# ECG_NEMO_final.net
KiCad netlist of a schematic drawn in Altium Designer
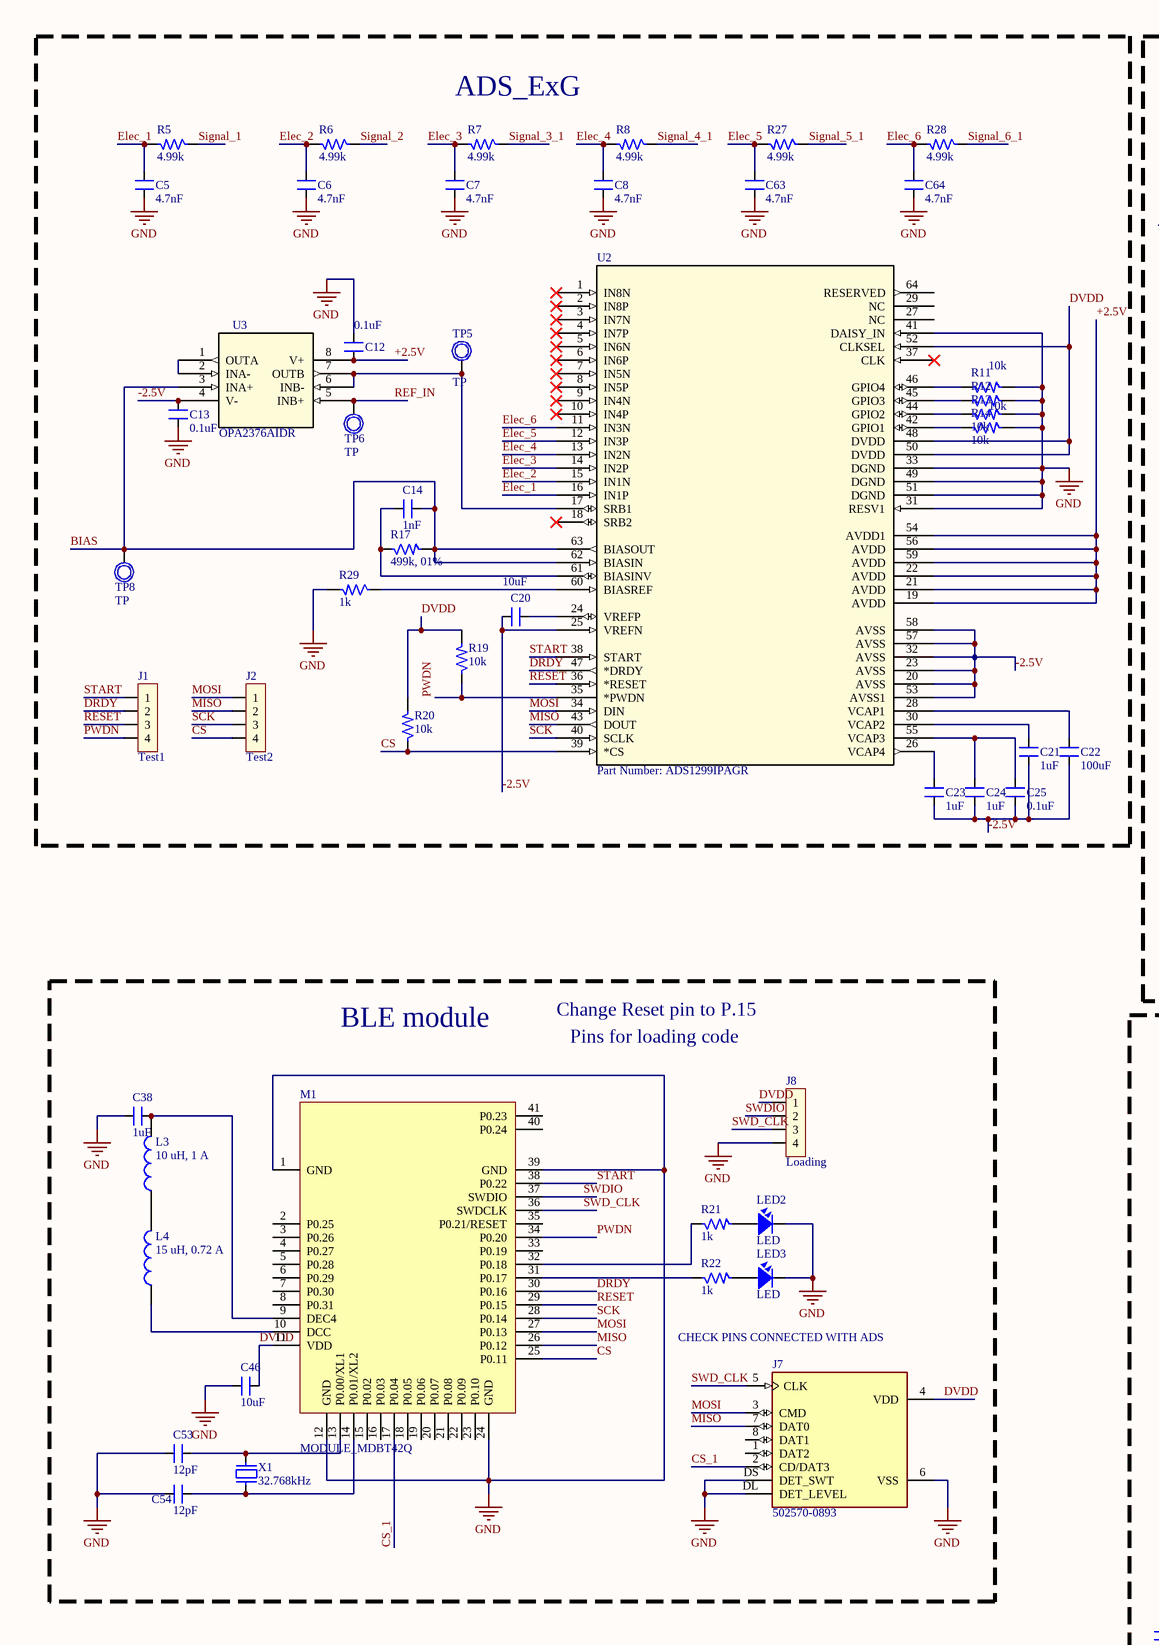
[diagram p0: ECG_NEMO_final.schdoc, left]
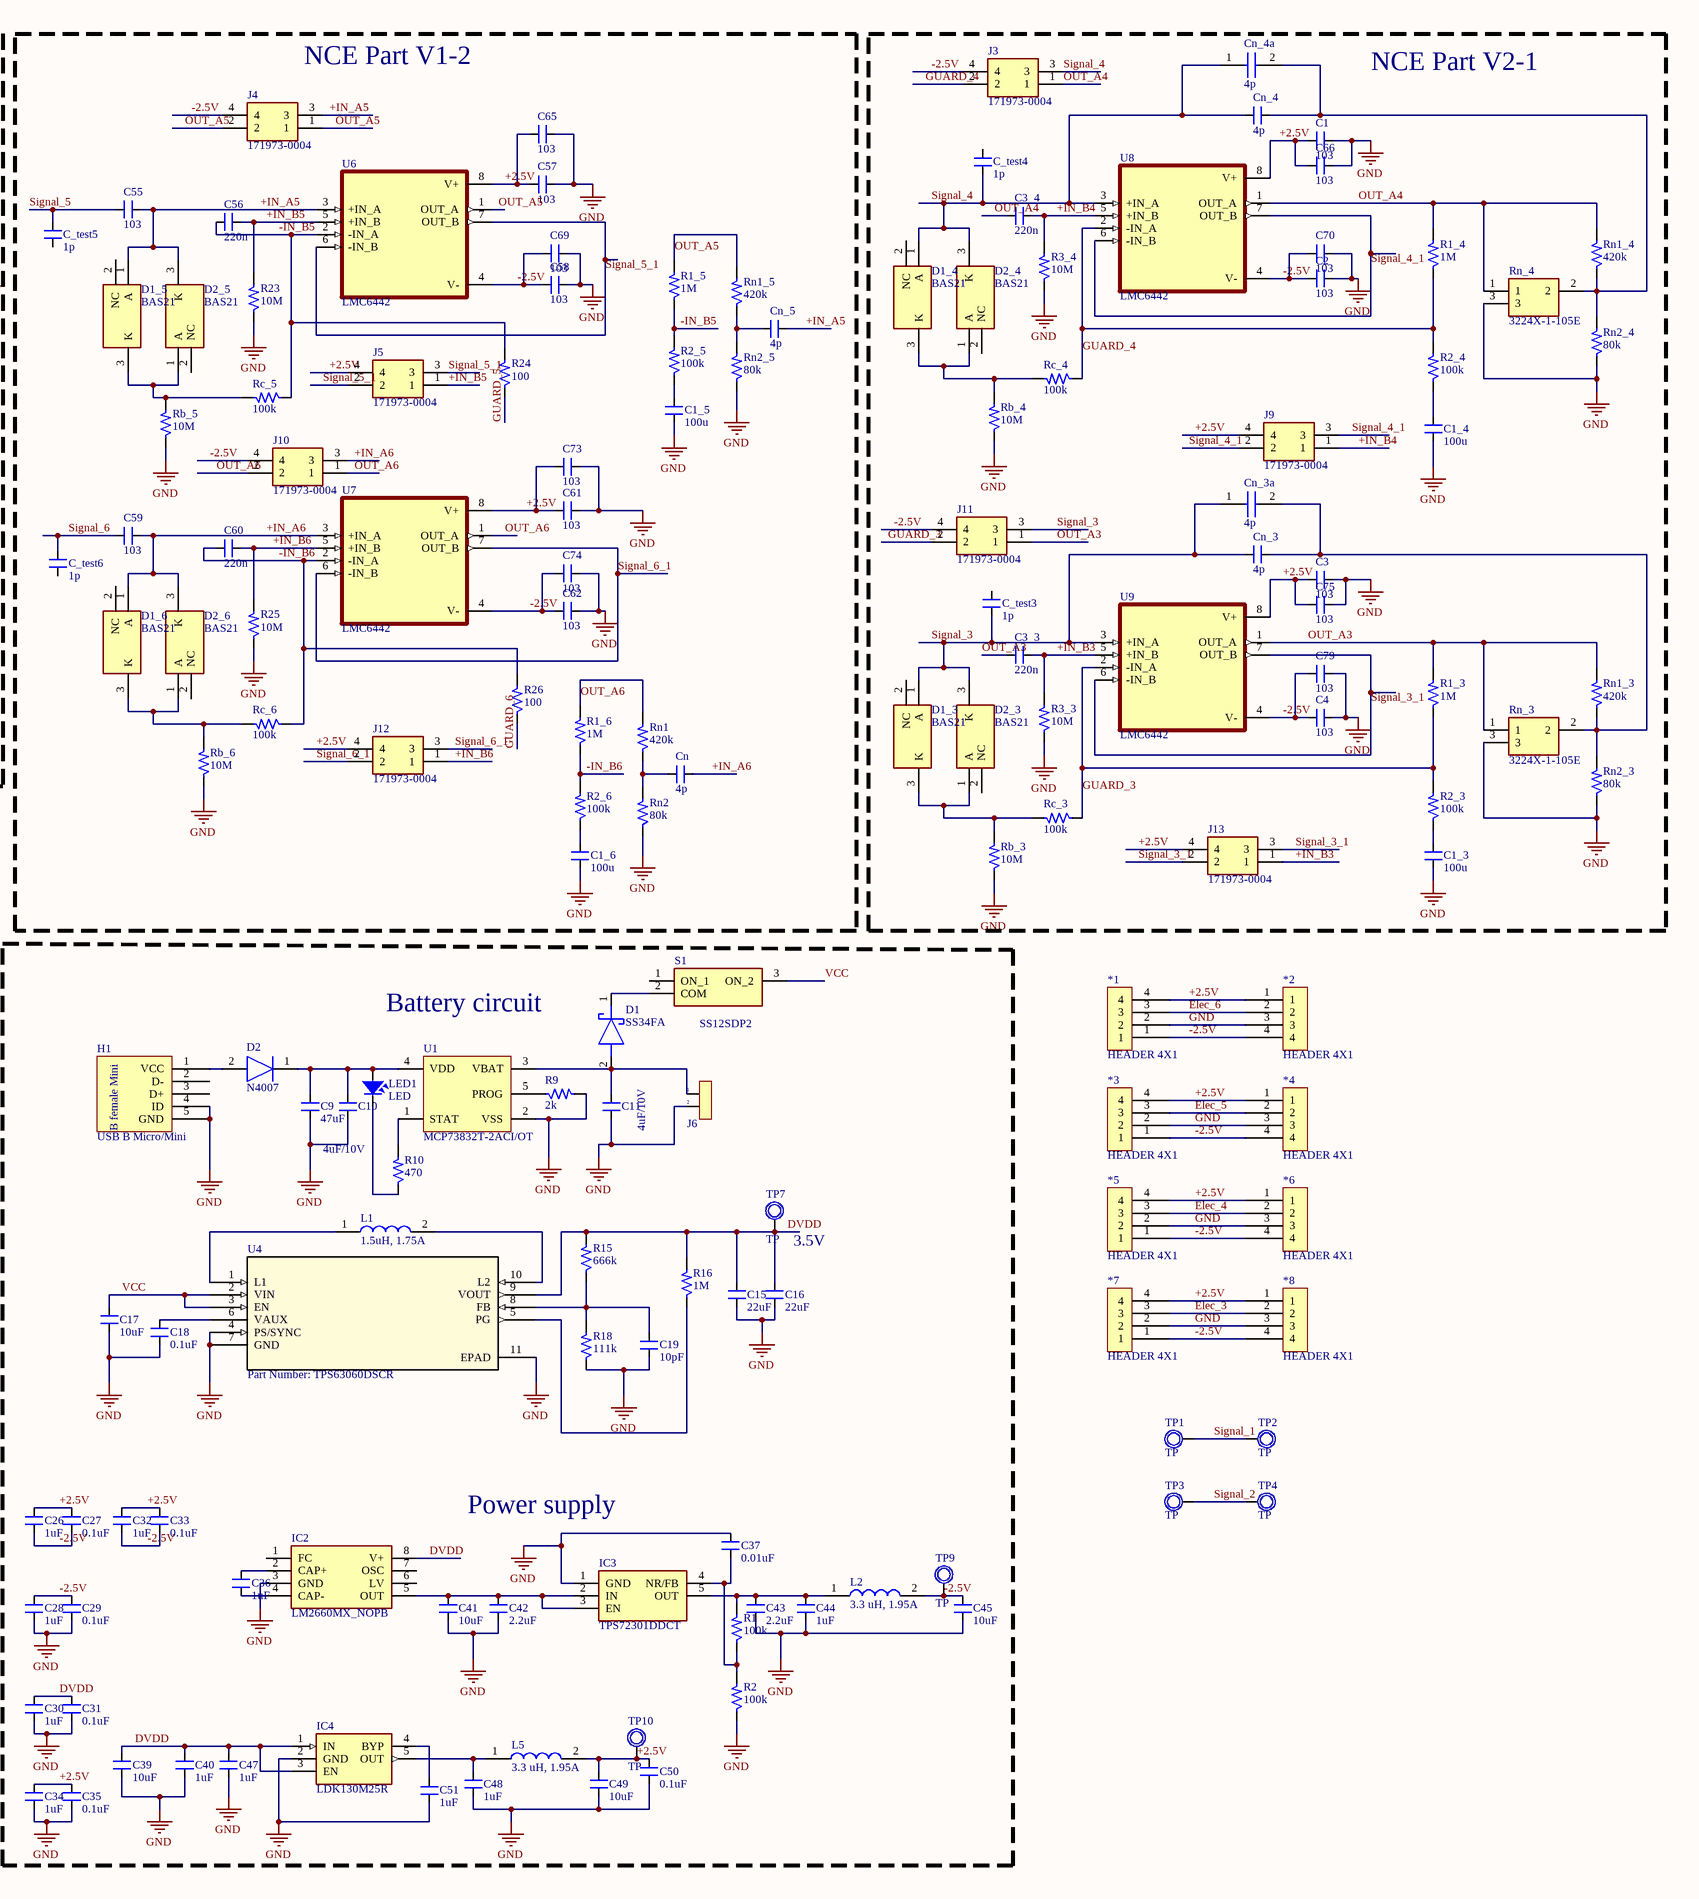
[diagram p1: ECG_NEMO_final.schdoc, right]

(export (version "E")
  (design (tool "Eeschema 10.0.6"))
  (components
    (comp (ref "*1") (value "HEADER 4X1") (footprint "HEADER4X1") (libsource (lib "") (part "HEADER 4X1_1")))
    (comp (ref "*2")
      (value "HEADER 4X1")
      (footprint "HEADER4X1")
      (libsource (lib "TechMT.VN_Lib_Project v1.0") (part "HEADER 4X1"))
    )
    (comp (ref "*3") (value "HEADER 4X1") (footprint "HEADER4X1") (libsource (lib "") (part "HEADER 4X1_1")))
    (comp (ref "*4")
      (value "HEADER 4X1")
      (footprint "HEADER4X1")
      (libsource (lib "TechMT.VN_Lib_Project v1.0") (part "HEADER 4X1"))
    )
    (comp (ref "*5") (value "HEADER 4X1") (footprint "HEADER4X1") (libsource (lib "") (part "HEADER 4X1_1")))
    (comp (ref "*6")
      (value "HEADER 4X1")
      (footprint "HEADER4X1")
      (libsource (lib "TechMT.VN_Lib_Project v1.0") (part "HEADER 4X1"))
    )
    (comp (ref "*7") (value "HEADER 4X1") (footprint "HEADER4X1") (libsource (lib "") (part "HEADER 4X1_1")))
    (comp (ref "*8")
      (value "HEADER 4X1")
      (footprint "HEADER4X1")
      (libsource (lib "TechMT.VN_Lib_Project v1.0") (part "HEADER 4X1"))
    )
    (comp (ref "C1")
      (value "103")
      (footprint "SM-0805")
      (description "Cap SMD")
      (libsource (lib "VioletofSun") (part "CM"))
    )
    (comp (ref "C1_3")
      (value "100u")
      (footprint "SM-0805")
      (description "Cap SMD")
      (libsource (lib "VioletofSun") (part "CM"))
    )
    (comp (ref "C1_4")
      (value "100u")
      (footprint "SM-0805")
      (description "Cap SMD")
      (libsource (lib "VioletofSun") (part "CM"))
    )
    (comp (ref "C1_5")
      (value "100u")
      (footprint "SM-0805")
      (description "Cap SMD")
      (libsource (lib "VioletofSun") (part "CM"))
    )
    (comp (ref "C1_6")
      (value "100u")
      (footprint "SM-0805")
      (description "Cap SMD")
      (libsource (lib "VioletofSun") (part "CM"))
    )
    (comp (ref "C2")
      (value "103")
      (footprint "SM-0805")
      (description "Cap SMD")
      (libsource (lib "VioletofSun") (part "CM"))
    )
    (comp (ref "C3")
      (value "103")
      (footprint "SM-0805")
      (description "Cap SMD")
      (libsource (lib "VioletofSun") (part "CM"))
    )
    (comp (ref "C3_3")
      (value "220n")
      (footprint "SM-0805")
      (description "Cap SMD")
      (libsource (lib "VioletofSun") (part "CM"))
    )
    (comp (ref "C3_4")
      (value "220n")
      (footprint "SM-0805")
      (description "Cap SMD")
      (libsource (lib "VioletofSun") (part "CM"))
    )
    (comp (ref "C4")
      (value "103")
      (footprint "SM-0805")
      (description "Cap SMD")
      (libsource (lib "VioletofSun") (part "CM"))
    )
    (comp (ref "C5")
      (value "4.7nF")
      (footprint "SM-0805")
      (description "Cap SMD")
      (libsource (lib "VioletofSun") (part "CM"))
    )
    (comp (ref "C6")
      (value "4.7nF")
      (footprint "SM-0805")
      (description "Cap SMD")
      (libsource (lib "VioletofSun") (part "CM"))
    )
    (comp (ref "C7")
      (value "4.7nF")
      (footprint "SM-0805")
      (description "Cap SMD")
      (libsource (lib "VioletofSun") (part "CM"))
    )
    (comp (ref "C8")
      (value "4.7nF")
      (footprint "SM-0805")
      (description "Cap SMD")
      (libsource (lib "VioletofSun") (part "CM"))
    )
    (comp (ref "C9")
      (value "47uF")
      (footprint "SM-0805")
      (description "Cap SMD")
      (libsource (lib "VioletofSun") (part "CM"))
    )
    (comp (ref "C10")
      (value "4uF/10V")
      (footprint "SM-0805")
      (description "Cap SMD")
      (libsource (lib "VioletofSun") (part "CM"))
    )
    (comp (ref "C11")
      (value "4uF/10V")
      (footprint "SM-0805")
      (description "Cap SMD")
      (libsource (lib "VioletofSun") (part "CM"))
    )
    (comp (ref "C12")
      (value "0.1uF")
      (footprint "SM-0805")
      (description "Cap SMD")
      (libsource (lib "VioletofSun") (part "CM"))
    )
    (comp (ref "C13")
      (value "0.1uF")
      (footprint "SM-0805")
      (description "Cap SMD")
      (libsource (lib "VioletofSun") (part "CM"))
    )
    (comp (ref "C14")
      (value "1nF")
      (footprint "SM-0805")
      (description "Cap SMD")
      (libsource (lib "VioletofSun") (part "CM"))
    )
    (comp (ref "C15")
      (value "22uF")
      (footprint "SM-0805")
      (description "Cap SMD")
      (libsource (lib "VioletofSun") (part "CM"))
    )
    (comp (ref "C16")
      (value "22uF")
      (footprint "SM-0805")
      (description "Cap SMD")
      (libsource (lib "VioletofSun") (part "CM"))
    )
    (comp (ref "C17")
      (value "10uF")
      (footprint "SM-0805")
      (description "Cap SMD")
      (libsource (lib "VioletofSun") (part "CM"))
    )
    (comp (ref "C18")
      (value "0.1uF")
      (footprint "SM-0805")
      (description "Cap SMD")
      (libsource (lib "VioletofSun") (part "CM"))
    )
    (comp (ref "C19")
      (value "10pF")
      (footprint "SM-0805")
      (description "Cap SMD")
      (libsource (lib "VioletofSun") (part "CM"))
    )
    (comp (ref "C20")
      (value "10uF")
      (footprint "SM-0805")
      (description "Cap SMD")
      (libsource (lib "VioletofSun") (part "CM"))
    )
    (comp (ref "C21")
      (value "1uF")
      (footprint "SM-0805")
      (description "Cap SMD")
      (libsource (lib "VioletofSun") (part "CM"))
    )
    (comp (ref "C22")
      (value "100uF")
      (footprint "SM-0805")
      (description "Cap SMD")
      (libsource (lib "VioletofSun") (part "CM"))
    )
    (comp (ref "C23")
      (value "1uF")
      (footprint "SM-0805")
      (description "Cap SMD")
      (libsource (lib "VioletofSun") (part "CM"))
    )
    (comp (ref "C24")
      (value "1uF")
      (footprint "SM-0805")
      (description "Cap SMD")
      (libsource (lib "VioletofSun") (part "CM"))
    )
    (comp (ref "C25")
      (value "0.1uF")
      (footprint "SM-0805")
      (description "Cap SMD")
      (libsource (lib "VioletofSun") (part "CM"))
    )
    (comp (ref "C26")
      (value "1uF")
      (footprint "SM-0805")
      (description "Cap SMD")
      (libsource (lib "VioletofSun") (part "CM"))
    )
    (comp (ref "C27")
      (value "0.1uF")
      (footprint "SM-0805")
      (description "Cap SMD")
      (libsource (lib "VioletofSun") (part "CM"))
    )
    (comp (ref "C28")
      (value "1uF")
      (footprint "SM-0805")
      (description "Cap SMD")
      (libsource (lib "VioletofSun") (part "CM"))
    )
    (comp (ref "C29")
      (value "0.1uF")
      (footprint "SM-0805")
      (description "Cap SMD")
      (libsource (lib "VioletofSun") (part "CM"))
    )
    (comp (ref "C30")
      (value "1uF")
      (footprint "SM-0805")
      (description "Cap SMD")
      (libsource (lib "VioletofSun") (part "CM"))
    )
    (comp (ref "C31")
      (value "0.1uF")
      (footprint "SM-0805")
      (description "Cap SMD")
      (libsource (lib "VioletofSun") (part "CM"))
    )
    (comp (ref "C32")
      (value "1uF")
      (footprint "SM-0805")
      (description "Cap SMD")
      (libsource (lib "VioletofSun") (part "CM"))
    )
    (comp (ref "C33")
      (value "0.1uF")
      (footprint "SM-0805")
      (description "Cap SMD")
      (libsource (lib "VioletofSun") (part "CM"))
    )
    (comp (ref "C34")
      (value "1uF")
      (footprint "SM-0805")
      (description "Cap SMD")
      (libsource (lib "VioletofSun") (part "CM"))
    )
    (comp (ref "C35")
      (value "0.1uF")
      (footprint "SM-0805")
      (description "Cap SMD")
      (libsource (lib "VioletofSun") (part "CM"))
    )
    (comp (ref "C36")
      (value "1uF")
      (footprint "SM-0805")
      (description "Cap SMD")
      (libsource (lib "VioletofSun") (part "CM"))
    )
    (comp (ref "C37")
      (value "0.01uF")
      (footprint "SM-0805")
      (description "Cap SMD")
      (libsource (lib "VioletofSun") (part "CM"))
    )
    (comp (ref "C38")
      (value "1uF")
      (footprint "SM-0805")
      (description "Cap SMD")
      (libsource (lib "VioletofSun") (part "CM"))
    )
    (comp (ref "C39")
      (value "10uF")
      (footprint "SM-0805")
      (description "Cap SMD")
      (libsource (lib "VioletofSun") (part "CM"))
    )
    (comp (ref "C40")
      (value "1uF")
      (footprint "SM-0805")
      (description "Cap SMD")
      (libsource (lib "VioletofSun") (part "CM"))
    )
    (comp (ref "C41")
      (value "10uF")
      (footprint "SM-0805")
      (description "Cap SMD")
      (libsource (lib "VioletofSun") (part "CM"))
    )
    (comp (ref "C42")
      (value "2.2uF")
      (footprint "SM-0805")
      (description "Cap SMD")
      (libsource (lib "VioletofSun") (part "CM"))
    )
    (comp (ref "C43")
      (value "2.2uF")
      (footprint "SM-0805")
      (description "Cap SMD")
      (libsource (lib "VioletofSun") (part "CM"))
    )
    (comp (ref "C44")
      (value "1uF")
      (footprint "SM-0805")
      (description "Cap SMD")
      (libsource (lib "VioletofSun") (part "CM"))
    )
    (comp (ref "C45")
      (value "10uF")
      (footprint "SM-0805")
      (description "Cap SMD")
      (libsource (lib "VioletofSun") (part "CM"))
    )
    (comp (ref "C46")
      (value "10uF")
      (footprint "SM-0805")
      (description "Cap SMD")
      (libsource (lib "VioletofSun") (part "CM"))
    )
    (comp (ref "C47")
      (value "1uF")
      (footprint "SM-0805")
      (description "Cap SMD")
      (libsource (lib "VioletofSun") (part "CM"))
    )
    (comp (ref "C48")
      (value "1uF")
      (footprint "SM-0805")
      (description "Cap SMD")
      (libsource (lib "VioletofSun") (part "CM"))
    )
    (comp (ref "C49")
      (value "10uF")
      (footprint "SM-0805")
      (description "Cap SMD")
      (libsource (lib "VioletofSun") (part "CM"))
    )
    (comp (ref "C50")
      (value "0.1uF")
      (footprint "SM-0805")
      (description "Cap SMD")
      (libsource (lib "VioletofSun") (part "CM"))
    )
    (comp (ref "C51")
      (value "1uF")
      (footprint "SM-0805")
      (description "Cap SMD")
      (libsource (lib "VioletofSun") (part "CM"))
    )
    (comp (ref "C53")
      (value "12pF")
      (footprint "SM-0805")
      (description "Cap SMD")
      (libsource (lib "VioletofSun") (part "CM"))
    )
    (comp (ref "C54")
      (value "12pF")
      (footprint "SM-0805")
      (description "Cap SMD")
      (libsource (lib "VioletofSun") (part "CM"))
    )
    (comp (ref "C55")
      (value "103")
      (footprint "SM-0805")
      (description "Cap SMD")
      (libsource (lib "Free Documents") (part "CM_5"))
    )
    (comp (ref "C56")
      (value "220n")
      (footprint "SM-0805")
      (description "Cap SMD")
      (libsource (lib "VioletofSun") (part "CM"))
    )
    (comp (ref "C57")
      (value "103")
      (footprint "SM-0805")
      (description "Cap SMD")
      (libsource (lib "VioletofSun") (part "CM"))
    )
    (comp (ref "C58")
      (value "103")
      (footprint "SM-0805")
      (description "Cap SMD")
      (libsource (lib "VioletofSun") (part "CM"))
    )
    (comp (ref "C59")
      (value "103")
      (footprint "SM-0805")
      (description "Cap SMD")
      (libsource (lib "VioletofSun") (part "CM"))
    )
    (comp (ref "C60")
      (value "220n")
      (footprint "SM-0805")
      (description "Cap SMD")
      (libsource (lib "VioletofSun") (part "CM"))
    )
    (comp (ref "C61")
      (value "103")
      (footprint "SM-0805")
      (description "Cap SMD")
      (libsource (lib "VioletofSun") (part "CM"))
    )
    (comp (ref "C62")
      (value "103")
      (footprint "SM-0805")
      (description "Cap SMD")
      (libsource (lib "VioletofSun") (part "CM"))
    )
    (comp (ref "C63")
      (value "4.7nF")
      (footprint "SM-0805")
      (description "Cap SMD")
      (libsource (lib "VioletofSun") (part "CM"))
    )
    (comp (ref "C64")
      (value "4.7nF")
      (footprint "SM-0805")
      (description "Cap SMD")
      (libsource (lib "VioletofSun") (part "CM"))
    )
    (comp (ref "C65")
      (value "103")
      (footprint "SM-0805")
      (description "Cap SMD")
      (libsource (lib "VioletofSun") (part "CM"))
    )
    (comp (ref "C66")
      (value "103")
      (footprint "SM-0805")
      (description "Cap SMD")
      (libsource (lib "VioletofSun") (part "CM"))
    )
    (comp (ref "C69")
      (value "103")
      (footprint "SM-0805")
      (description "Cap SMD")
      (libsource (lib "VioletofSun") (part "CM"))
    )
    (comp (ref "C70")
      (value "103")
      (footprint "SM-0805")
      (description "Cap SMD")
      (libsource (lib "VioletofSun") (part "CM"))
    )
    (comp (ref "C73")
      (value "103")
      (footprint "SM-0805")
      (description "Cap SMD")
      (libsource (lib "VioletofSun") (part "CM"))
    )
    (comp (ref "C74")
      (value "103")
      (footprint "SM-0805")
      (description "Cap SMD")
      (libsource (lib "VioletofSun") (part "CM"))
    )
    (comp (ref "C75")
      (value "103")
      (footprint "SM-0805")
      (description "Cap SMD")
      (libsource (lib "VioletofSun") (part "CM"))
    )
    (comp (ref "C79")
      (value "103")
      (footprint "SM-0805")
      (description "Cap SMD")
      (libsource (lib "VioletofSun") (part "CM"))
    )
    (comp (ref "Cn")
      (value "4p")
      (footprint "SM-0805")
      (description "Cap SMD")
      (libsource (lib "VioletofSun") (part "CM"))
    )
    (comp (ref "Cn_3")
      (value "4p")
      (footprint "SM-0805")
      (description "Cap SMD")
      (libsource (lib "VioletofSun") (part "CM"))
    )
    (comp (ref "Cn_3a")
      (value "4p")
      (footprint "Var_Cap-JZ100:JZ100")
      (description "Capacitor")
      (fields
        (field (name "MANUFACTURER_PART_NUMBER") "JZ100")
        (field (name "MOUSER PART NUMBER") "768-JZ100")
      )
      (libsource (lib "Var_Cap-JZ100") (part "JZ100"))
    )
    (comp (ref "Cn_4")
      (value "4p")
      (footprint "SM-0805")
      (description "Cap SMD")
      (libsource (lib "VioletofSun") (part "CM"))
    )
    (comp (ref "Cn_4a")
      (value "4p")
      (footprint "Var_Cap-JZ100:JZ100")
      (description "Capacitor")
      (fields
        (field (name "MANUFACTURER_PART_NUMBER") "JZ100")
        (field (name "MOUSER PART NUMBER") "768-JZ100")
      )
      (libsource (lib "Var_Cap-JZ100") (part "JZ100"))
    )
    (comp (ref "Cn_5")
      (value "4p")
      (footprint "SM-0805")
      (description "Cap SMD")
      (libsource (lib "VioletofSun") (part "CM"))
    )
    (comp (ref "C_test3")
      (value "1p")
      (footprint "SM-0805")
      (description "Cap SMD")
      (libsource (lib "Flex-PCB-fmECG") (part "CM_5"))
    )
    (comp (ref "C_test4")
      (value "1p")
      (footprint "SM-0805")
      (description "Cap SMD")
      (libsource (lib "Flex-PCB-fmECG") (part "CM_5"))
    )
    (comp (ref "C_test5")
      (value "1p")
      (footprint "SM-0805")
      (description "Cap SMD")
      (libsource (lib "Flex-PCB-fmECG") (part "CM_5"))
    )
    (comp (ref "C_test6")
      (value "1p")
      (footprint "SM-0805")
      (description "Cap SMD")
      (libsource (lib "Flex-PCB-fmECG") (part "CM_5"))
    )
    (comp (ref "D1")
      (value "SS34FA")
      (footprint "SODFL3618X143N")
      (description "Schottky Diode")
      (fields (field (name "MOUSER PART NUMBER") "512-SS34FA"))
      (libsource (lib "*") (part "SS34FA"))
    )
    (comp (ref "D1_3")
      (value "BAS21")
      (footprint "BAS21:SOT95P240X120-3N")
      (description "Diode")
      (fields (field (name "MOUSER PART NUMBER") "512-BAS21"))
      (libsource (lib "") (part "BAS21_1"))
    )
    (comp (ref "D1_4")
      (value "BAS21")
      (footprint "BAS21:SOT95P240X120-3N")
      (description "Diode")
      (fields (field (name "MOUSER PART NUMBER") "512-BAS21"))
      (libsource (lib "") (part "BAS21_1"))
    )
    (comp (ref "D1_5")
      (value "BAS21")
      (footprint "BAS21:SOT95P240X120-3N")
      (description "Diode")
      (fields (field (name "MOUSER PART NUMBER") "512-BAS21"))
      (libsource (lib "") (part "BAS21_1"))
    )
    (comp (ref "D1_6")
      (value "BAS21")
      (footprint "BAS21:SOT95P240X120-3N")
      (description "Diode")
      (fields (field (name "MOUSER PART NUMBER") "512-BAS21"))
      (libsource (lib "") (part "BAS21_1"))
    )
    (comp (ref "D2")
      (value "N4007")
      (footprint "DIOM5025X220N")
      (description "Diode")
      (fields
        (field (name "MOUSER PART NUMBER") "346-EC11FS2")
        (field (name "MANUFACTURER_PART_NUMBER") "EC11FS2")
      )
      (libsource (lib "*") (part "EC11FS2"))
    )
    (comp (ref "D2_3")
      (value "BAS21")
      (footprint "BAS21:SOT95P240X120-3N")
      (description "Diode")
      (fields (field (name "MOUSER PART NUMBER") "512-BAS21"))
      (libsource (lib "BAS21") (part "BAS21"))
    )
    (comp (ref "D2_4")
      (value "BAS21")
      (footprint "BAS21:SOT95P240X120-3N")
      (description "Diode")
      (fields (field (name "MOUSER PART NUMBER") "512-BAS21"))
      (libsource (lib "BAS21") (part "BAS21"))
    )
    (comp (ref "D2_5")
      (value "BAS21")
      (footprint "BAS21:SOT95P240X120-3N")
      (description "Diode")
      (fields (field (name "MOUSER PART NUMBER") "512-BAS21"))
      (libsource (lib "BAS21") (part "BAS21"))
    )
    (comp (ref "D2_6")
      (value "BAS21")
      (footprint "BAS21:SOT95P240X120-3N")
      (description "Diode")
      (fields (field (name "MOUSER PART NUMBER") "512-BAS21"))
      (libsource (lib "BAS21") (part "BAS21"))
    )
    (comp (ref "H1")
      (value "USB B Micro/Mini")
      (footprint "USB-B-MICRO-female Tai02")
      (description "USB B Female Micro/Mini SMD")
      (libsource (lib "mylib") (part "USB B Female Micro/Mini SMD"))
    )
    (comp (ref "IC2")
      (value "LM2660MX_NOPB")
      (footprint "LM2660MX:SOIC127P600X175-8N")
      (description "Integrated Circuit")
      (fields (field (name "MANUFACTURER_PART_NUMBER") "LM2660MX NOPB"))
      (libsource (lib "LM2660MX") (part "LM2660MX_NOPB"))
    )
    (comp (ref "IC3")
      (value "TPS72301DDCT")
      (footprint "TPS72301DDCT:SOT95P280X110-5N")
      (description "Integrated Circuit")
      (fields (field (name "MOUSER PART NUMBER") "595-TPS72301DDCT"))
      (libsource (lib "TPS72301DDCT") (part "TPS72301DDCT"))
    )
    (comp (ref "IC4")
      (value "LDK130M25R")
      (footprint "LDK130M25R:SOT95P280X145-5N")
      (description "Integrated Circuit")
      (fields (field (name "MOUSER PART NUMBER") "511-LDK130M25R"))
      (libsource (lib "LDK130M25R") (part "LDK130M25R"))
    )
    (comp (ref "J1")
      (value "Test1")
      (footprint "sip4")
      (description "Connector 4")
      (libsource (lib "VioletofSun") (part "JP4"))
    )
    (comp (ref "J2")
      (value "Test2")
      (footprint "sip4")
      (description "Connector 4")
      (libsource (lib "VioletofSun") (part "JP4"))
    )
    (comp (ref "J3")
      (value "171973-0004")
      (footprint "Head4_SMD:1719730004")
      (description "Connector")
      (fields (field (name "MOUSER PART NUMBER") "538-171973-0004"))
      (libsource (lib "Head4_SMD") (part "171973-0004"))
    )
    (comp (ref "J4")
      (value "171973-0004")
      (footprint "Head4_SMD:1719730004")
      (description "Connector")
      (fields (field (name "MOUSER PART NUMBER") "538-171973-0004"))
      (libsource (lib "Head4_SMD") (part "171973-0004"))
    )
    (comp (ref "J5")
      (value "171973-0004")
      (footprint "Head4_SMD:1719730004")
      (description "Connector")
      (fields (field (name "MOUSER PART NUMBER") "538-171973-0004"))
      (libsource (lib "Head4_SMD") (part "171973-0004"))
    )
    (comp (ref "J6")
      (value "Jumper 2")
      (footprint "J2_Jst SH_1mm")
      (libsource (lib "VioletofSun") (part "JP 2"))
    )
    (comp (ref "J7")
      (value "502570-0893")
      (footprint "MOLEX_502570-0893")
      (description "10 _8 + 2_ Position Card Connector Secure Digital - microSDâ„¢ Surface Mount, Right Angle Gold")
      (fields (field (name "MF") "Molex"))
      (libsource (lib "502570-0893") (part "502570-0893"))
    )
    (comp (ref "J8")
      (value "Loading")
      (footprint "sip4")
      (description "Connector 4")
      (libsource (lib "VioletofSun") (part "JP4"))
    )
    (comp (ref "J9")
      (value "171973-0004")
      (footprint "Head4_SMD:1719730004")
      (description "Connector")
      (fields (field (name "MOUSER PART NUMBER") "538-171973-0004"))
      (libsource (lib "Head4_SMD") (part "171973-0004"))
    )
    (comp (ref "J10")
      (value "171973-0004")
      (footprint "Head4_SMD:1719730004")
      (description "Connector")
      (fields (field (name "MOUSER PART NUMBER") "538-171973-0004"))
      (libsource (lib "Head4_SMD") (part "171973-0004"))
    )
    (comp (ref "J11")
      (value "171973-0004")
      (footprint "Head4_SMD:1719730004")
      (description "Connector")
      (fields (field (name "MOUSER PART NUMBER") "538-171973-0004"))
      (libsource (lib "Head4_SMD") (part "171973-0004"))
    )
    (comp (ref "J12")
      (value "171973-0004")
      (footprint "Head4_SMD:1719730004")
      (description "Connector")
      (fields (field (name "MOUSER PART NUMBER") "538-171973-0004"))
      (libsource (lib "Head4_SMD") (part "171973-0004"))
    )
    (comp (ref "J13")
      (value "171973-0004")
      (footprint "Head4_SMD:1719730004")
      (description "Connector")
      (fields (field (name "MOUSER PART NUMBER") "538-171973-0004"))
      (libsource (lib "Head4_SMD") (part "171973-0004"))
    )
    (comp (ref "L1")
      (value "1.5uH, 1.75A")
      (footprint "744031001:WE-TPC_381692")
      (description "Inductor")
      (fields
        (field (name "MANUFACTURER_PART_NUMBER") "744031001")
        (field (name "MOUSER PART NUMBER") "710-744031001")
      )
      (libsource (lib "744031001") (part "744031001"))
    )
    (comp (ref "L2")
      (value "3.3 uH, 1.95A")
      (footprint "Inductor-744042003:WE-TPC_4818/482892")
      (description "Inductor")
      (fields
        (field (name "MANUFACTURER_PART_NUMBER") "744042003")
        (field (name "MOUSER PART NUMBER") "710-744042003")
      )
      (libsource (lib "Inductor-744042003") (part "744042003"))
    )
    (comp (ref "L3")
      (value "10 uH, 1 A")
      (footprint "WE-TPC_2828")
      (description "SMT Shielded Tiny Power Inductor WE-TPC, size 2828, 10 uH, 1 A")
      (fields (field (name "PART NUMBER") "744025100") (field (name "PUBLISHER") "Wurth Elektronik"))
      (libsource (lib "ALTIUM-WE-TPC-rev18a") (part "744025100"))
    )
    (comp (ref "L4")
      (value "15 uH, 0.72 A")
      (footprint "WE-TPC_2828")
      (description "SMT Shielded Tiny Power Inductor WE-TPC, size 2828, 15 uH, 0.72 A")
      (fields (field (name "PART NUMBER") "744025150") (field (name "PUBLISHER") "Wurth Elektronik"))
      (libsource (lib "ALTIUM-WE-TPC-rev18a") (part "744025150"))
    )
    (comp (ref "L5")
      (value "3.3 uH, 1.95A")
      (footprint "Inductor-744042003:WE-TPC_4818/482892")
      (description "Inductor")
      (fields
        (field (name "MANUFACTURER_PART_NUMBER") "744042003")
        (field (name "MOUSER PART NUMBER") "710-744042003")
      )
      (libsource (lib "Inductor-744042003") (part "744042003"))
    )
    (comp (ref "LED1")
      (value "LED")
      (footprint "SM-0805")
      (description "LED Single colour Green and Red")
      (libsource (lib "") (part "LED_1"))
    )
    (comp (ref "LED2")
      (value "LED")
      (footprint "led0805")
      (description "LED Single colour Green and Red")
      (libsource (lib "VioletofSun") (part "LED"))
    )
    (comp (ref "LED3")
      (value "LED")
      (footprint "led0805")
      (description "LED Single colour Green and Red")
      (libsource (lib "VioletofSun") (part "LED"))
    )
    (comp (ref "M1")
      (value "MODULE_MDBT42Q")
      (footprint "PCB_MDBT42Q_10X16")
      (description "MDBT42Q")
      (libsource (lib "MDBT42Q_SCHLIB_181015") (part "MODULE_MDBT42Q"))
    )
    (comp (ref "R1")
      (value "100k")
      (footprint "SM-0805")
      (description "Resistor 1/4W")
      (libsource (lib "PCB_NEMO_v1-2_v2-1") (part "R"))
    )
    (comp (ref "R1_3")
      (value "1M")
      (footprint "SM-0805")
      (description "Resistor 1/4W")
      (libsource (lib "VioletofSun") (part "R"))
    )
    (comp (ref "R1_4")
      (value "1M")
      (footprint "SM-0805")
      (description "Resistor 1/4W")
      (libsource (lib "VioletofSun") (part "R"))
    )
    (comp (ref "R1_5")
      (value "1M")
      (footprint "SM-0805")
      (description "Resistor 1/4W")
      (libsource (lib "VioletofSun") (part "R"))
    )
    (comp (ref "R1_6")
      (value "1M")
      (footprint "SM-0805")
      (description "Resistor 1/4W")
      (libsource (lib "VioletofSun") (part "R"))
    )
    (comp (ref "R2")
      (value "100k")
      (footprint "SM-0805")
      (description "Resistor 1/4W")
      (libsource (lib "PCB_NEMO_v1-2_v2-1") (part "R"))
    )
    (comp (ref "R2_3")
      (value "100k")
      (footprint "SM-0805")
      (description "Resistor 1/4W")
      (libsource (lib "VioletofSun") (part "R"))
    )
    (comp (ref "R2_4")
      (value "100k")
      (footprint "SM-0805")
      (description "Resistor 1/4W")
      (libsource (lib "VioletofSun") (part "R"))
    )
    (comp (ref "R2_5")
      (value "100k")
      (footprint "SM-0805")
      (description "Resistor 1/4W")
      (libsource (lib "VioletofSun") (part "R"))
    )
    (comp (ref "R2_6")
      (value "100k")
      (footprint "SM-0805")
      (description "Resistor 1/4W")
      (libsource (lib "VioletofSun") (part "R"))
    )
    (comp (ref "R3_3")
      (value "10M")
      (footprint "SM-0805")
      (description "Resistor 1/4W")
      (libsource (lib "VioletofSun") (part "R"))
    )
    (comp (ref "R3_4")
      (value "10M")
      (footprint "SM-0805")
      (description "Resistor 1/4W")
      (libsource (lib "VioletofSun") (part "R"))
    )
    (comp (ref "R5")
      (value "4.99k")
      (footprint "SM-0805")
      (description "Resistor 1/4W")
      (libsource (lib "VioletofSun") (part "R"))
    )
    (comp (ref "R6")
      (value "4.99k")
      (footprint "SM-0805")
      (description "Resistor 1/4W")
      (libsource (lib "VioletofSun") (part "R"))
    )
    (comp (ref "R7")
      (value "4.99k")
      (footprint "SM-0805")
      (description "Resistor 1/4W")
      (libsource (lib "VioletofSun") (part "R"))
    )
    (comp (ref "R8")
      (value "4.99k")
      (footprint "SM-0805")
      (description "Resistor 1/4W")
      (libsource (lib "VioletofSun") (part "R"))
    )
    (comp (ref "R9")
      (value "2k")
      (footprint "SM-0805")
      (description "Resistor 1/4W")
      (libsource (lib "VioletofSun") (part "R"))
    )
    (comp (ref "R10")
      (value "470")
      (footprint "SM-0805")
      (description "Resistor 1/4W")
      (libsource (lib "VioletofSun") (part "R"))
    )
    (comp (ref "R11")
      (value "10k")
      (footprint "SM-0805")
      (description "Resistor 1/4W")
      (libsource (lib "VioletofSun") (part "R"))
    )
    (comp (ref "R12")
      (value "10k")
      (footprint "SM-0805")
      (description "Resistor 1/4W")
      (libsource (lib "VioletofSun") (part "R"))
    )
    (comp (ref "R13")
      (value "10k")
      (footprint "SM-0805")
      (description "Resistor 1/4W")
      (libsource (lib "VioletofSun") (part "R"))
    )
    (comp (ref "R14")
      (value "10k")
      (footprint "SM-0805")
      (description "Resistor 1/4W")
      (libsource (lib "VioletofSun") (part "R"))
    )
    (comp (ref "R15")
      (value "666k")
      (footprint "SM-0805")
      (description "Resistor 1/4W")
      (libsource (lib "VioletofSun") (part "R"))
    )
    (comp (ref "R16")
      (value "1M")
      (footprint "SM-0805")
      (description "Resistor 1/4W")
      (libsource (lib "VioletofSun") (part "R"))
    )
    (comp (ref "R17")
      (value "499k, 01%")
      (footprint "SM-0805")
      (description "Resistor 1/4W")
      (libsource (lib "VioletofSun") (part "R"))
    )
    (comp (ref "R18")
      (value "111k")
      (footprint "SM-0805")
      (description "Resistor 1/4W")
      (libsource (lib "VioletofSun") (part "R"))
    )
    (comp (ref "R19")
      (value "10k")
      (footprint "SM-0805")
      (description "Resistor 1/4W")
      (libsource (lib "VioletofSun") (part "R"))
    )
    (comp (ref "R20")
      (value "10k")
      (footprint "SM-0805")
      (description "Resistor 1/4W")
      (libsource (lib "VioletofSun") (part "R"))
    )
    (comp (ref "R21")
      (value "1k")
      (footprint "SM-0805")
      (description "Resistor 1/4W")
      (libsource (lib "VioletofSun") (part "R"))
    )
    (comp (ref "R22")
      (value "1k")
      (footprint "SM-0805")
      (description "Resistor 1/4W")
      (libsource (lib "VioletofSun") (part "R"))
    )
    (comp (ref "R23")
      (value "10M")
      (footprint "SM-0805")
      (description "Resistor 1/4W")
      (libsource (lib "VioletofSun") (part "R"))
    )
    (comp (ref "R24")
      (value "100")
      (footprint "SM-0805")
      (description "Resistor 1/4W")
      (libsource (lib "VioletofSun") (part "R"))
    )
    (comp (ref "R25")
      (value "10M")
      (footprint "SM-0805")
      (description "Resistor 1/4W")
      (libsource (lib "VioletofSun") (part "R"))
    )
    (comp (ref "R26")
      (value "100")
      (footprint "SM-0805")
      (description "Resistor 1/4W")
      (libsource (lib "VioletofSun") (part "R"))
    )
    (comp (ref "R27")
      (value "4.99k")
      (footprint "SM-0805")
      (description "Resistor 1/4W")
      (libsource (lib "VioletofSun") (part "R"))
    )
    (comp (ref "R28")
      (value "4.99k")
      (footprint "SM-0805")
      (description "Resistor 1/4W")
      (libsource (lib "VioletofSun") (part "R"))
    )
    (comp (ref "R29")
      (value "1k")
      (footprint "SM-0805")
      (description "Resistor 1/4W")
      (libsource (lib "VioletofSun") (part "R"))
    )
    (comp (ref "Rb_3")
      (value "10M")
      (footprint "SM-0805")
      (description "Resistor 1/4W")
      (libsource (lib "VioletofSun") (part "R"))
    )
    (comp (ref "Rb_4")
      (value "10M")
      (footprint "SM-0805")
      (description "Resistor 1/4W")
      (libsource (lib "VioletofSun") (part "R"))
    )
    (comp (ref "Rb_5")
      (value "10M")
      (footprint "SM-0805")
      (description "Resistor 1/4W")
      (libsource (lib "VioletofSun") (part "R"))
    )
    (comp (ref "Rb_6")
      (value "10M")
      (footprint "SM-0805")
      (description "Resistor 1/4W")
      (libsource (lib "VioletofSun") (part "R"))
    )
    (comp (ref "Rc_3")
      (value "100k")
      (footprint "SM-0805")
      (description "Resistor 1/4W")
      (libsource (lib "VioletofSun") (part "R"))
    )
    (comp (ref "Rc_4")
      (value "100k")
      (footprint "SM-0805")
      (description "Resistor 1/4W")
      (libsource (lib "VioletofSun") (part "R"))
    )
    (comp (ref "Rc_5")
      (value "100k")
      (footprint "SM-0805")
      (description "Resistor 1/4W")
      (libsource (lib "VioletofSun") (part "R"))
    )
    (comp (ref "Rc_6")
      (value "100k")
      (footprint "SM-0805")
      (description "Resistor 1/4W")
      (libsource (lib "VioletofSun") (part "R"))
    )
    (comp (ref "Rn1")
      (value "420k")
      (footprint "SM-0805")
      (description "Resistor 1/4W")
      (libsource (lib "VioletofSun") (part "R"))
    )
    (comp (ref "Rn1_3")
      (value "420k")
      (footprint "SM-0805")
      (description "Resistor 1/4W")
      (libsource (lib "VioletofSun") (part "R"))
    )
    (comp (ref "Rn1_4")
      (value "420k")
      (footprint "SM-0805")
      (description "Resistor 1/4W")
      (libsource (lib "VioletofSun") (part "R"))
    )
    (comp (ref "Rn1_5")
      (value "420k")
      (footprint "SM-0805")
      (description "Resistor 1/4W")
      (libsource (lib "VioletofSun") (part "R"))
    )
    (comp (ref "Rn2")
      (value "80k")
      (footprint "SM-0805")
      (description "Resistor 1/4W")
      (libsource (lib "VioletofSun") (part "R"))
    )
    (comp (ref "Rn2_3")
      (value "80k")
      (footprint "SM-0805")
      (description "Resistor 1/4W")
      (libsource (lib "VioletofSun") (part "R"))
    )
    (comp (ref "Rn2_4")
      (value "80k")
      (footprint "SM-0805")
      (description "Resistor 1/4W")
      (libsource (lib "VioletofSun") (part "R"))
    )
    (comp (ref "Rn2_5")
      (value "80k")
      (footprint "SM-0805")
      (description "Resistor 1/4W")
      (libsource (lib "VioletofSun") (part "R"))
    )
    (comp (ref "Rn_3")
      (value "3224X-1-105E")
      (footprint "3224X-1-504E:3224X1502E")
      (description "Resistor")
      (fields (field (name "MOUSER PART NUMBER") "652-3224X-1-105E"))
      (libsource (lib "3224X-1-504E") (part "3224X-1-105E"))
    )
    (comp (ref "Rn_4")
      (value "3224X-1-105E")
      (footprint "3224X-1-504E:3224X1502E")
      (description "Resistor")
      (fields (field (name "MOUSER PART NUMBER") "652-3224X-1-105E"))
      (libsource (lib "3224X-1-504E") (part "3224X-1-105E"))
    )
    (comp (ref "S1")
      (value "SS12SDP2")
      (footprint "SS12SDP2")
      (description "Switch")
      (fields (field (name "MOUSER PART NUMBER") "633-SS12SDP2"))
      (libsource (lib "*") (part "SS12SDP2"))
    )
    (comp (ref "TP1")
      (value "TP")
      (footprint "TP1")
      (description "Test Point")
      (libsource (lib "syhaunguyen") (part "TP1"))
    )
    (comp (ref "TP2")
      (value "TP")
      (footprint "TP1")
      (description "Test Point")
      (libsource (lib "") (part "TP1_1"))
    )
    (comp (ref "TP3")
      (value "TP")
      (footprint "TP1")
      (description "Test Point")
      (libsource (lib "syhaunguyen") (part "TP1"))
    )
    (comp (ref "TP4")
      (value "TP")
      (footprint "TP1")
      (description "Test Point")
      (libsource (lib "") (part "TP1_1"))
    )
    (comp (ref "TP5")
      (value "TP")
      (footprint "TP1")
      (description "Test Point")
      (libsource (lib "VioletofSun") (part "TP1"))
    )
    (comp (ref "TP6")
      (value "TP")
      (footprint "TP1")
      (description "Test Point")
      (libsource (lib "") (part "TP1_1"))
    )
    (comp (ref "TP7")
      (value "TP")
      (footprint "TP1")
      (description "Test Point")
      (libsource (lib "VioletofSun") (part "TP1"))
    )
    (comp (ref "TP8")
      (value "TP")
      (footprint "TP1")
      (description "Test Point")
      (libsource (lib "") (part "TP1_1"))
    )
    (comp (ref "TP9")
      (value "TP")
      (footprint "TP1")
      (description "Test Point")
      (libsource (lib "VioletofSun") (part "TP1"))
    )
    (comp (ref "TP10")
      (value "TP")
      (footprint "TP1")
      (description "Test Point")
      (libsource (lib "VioletofSun") (part "TP1"))
    )
    (comp (ref "U1")
      (value "MCP73832T-2ACI/OT")
      (footprint "SOT-23-OT5_N")
      (fields (field (name "PUBLISHER") "Altium Limited"))
      (libsource (lib "Microchip Power Mgt Battery Management") (part "MCP73832T-2ACI/OT"))
    )
    (comp (ref "U2")
      (value "Part Number: ADS1299IPAGR")
      (footprint "QFP50P1200X1200X120-64N")
      (description "No Description Available")
      (fields
        (field (name "MANUFACTURER_PART_NUMBER") "ADS1299IPAGR")
        (field (name "COPYRIGHT") "Copyright (C) 2018 Accelerated Designs. All rights reserved")
      )
      (libsource (lib "Flex-PCB-fmECG") (part "ADS1299IPAGR"))
    )
    (comp (ref "U3")
      (value "OPA2376AIDR")
      (footprint "D8")
      (description "No Description Available")
      (fields (field (name "COPYRIGHT") "Copyright (C) 2018 Accelerated Designs. All rights reserved"))
      (libsource (lib "2019-06-26_00-32-27") (part "OPA2376AIDR"))
    )
    (comp (ref "U4")
      (value "Part Number: TPS63060DSCR")
      (footprint "DSC10_1P70X2P15")
      (description "No Description Available")
      (fields
        (field (name "MANUFACTURER_PART_NUMBER") "TPS63060DSCR")
        (field (name "MANUFACTURER") "Texas Instruments")
        (field (name "COPYRIGHT") "Copyright (C) 2018 Accelerated Designs. All rights reserved")
      )
      (libsource (lib "2019-06-25_17-28-37") (part "TPS63060DSCR"))
    )
    (comp (ref "U6")
      (value "LMC6442")
      (footprint "SOIC127P599X175-8N")
      (description "10V, 0.1V/?C, High-Precision, Low-Power Operational Amplifier 8-SOIC")
      (fields (field (name "MF") "Texas Instruments") (field (name "MP") "OPA2277U"))
      (libsource (lib "OPA2277U") (part "OPA2277U"))
    )
    (comp (ref "U7")
      (value "LMC6442")
      (footprint "SOIC127P599X175-8N")
      (description "10V, 0.1V/?C, High-Precision, Low-Power Operational Amplifier 8-SOIC")
      (fields (field (name "MF") "Texas Instruments") (field (name "MP") "OPA2277U"))
      (libsource (lib "OPA2277U") (part "OPA2277U"))
    )
    (comp (ref "U8")
      (value "LMC6442")
      (footprint "SOIC127P599X175-8N")
      (description "10V, 0.1V/?C, High-Precision, Low-Power Operational Amplifier 8-SOIC")
      (fields (field (name "MF") "Texas Instruments") (field (name "MP") "OPA2277U"))
      (libsource (lib "Flex-PCB-fmECG") (part "OPA2277U"))
    )
    (comp (ref "U9")
      (value "LMC6442")
      (footprint "SOIC127P599X175-8N")
      (description "10V, 0.1V/?C, High-Precision, Low-Power Operational Amplifier 8-SOIC")
      (fields (field (name "MF") "Texas Instruments") (field (name "MP") "OPA2277U"))
      (libsource (lib "Flex-PCB-fmECG") (part "OPA2277U"))
    )
    (comp (ref "X1")
      (value "32.768kHz")
      (footprint "Crystal 32.768kHz SMD")
      (description "Crystal For all Crystal 2pin.")
      (libsource (lib "mylib") (part "Crystal"))
    )
  )
  (nets
    (net (code "1") (name "/+2.5V") (class "Default")
      (node (ref "*1") (pin "4") (pinfunction "4_4") (pintype "passive"))
      (node (ref "*2") (pin "1") (pinfunction "1_1") (pintype "passive"))
      (node (ref "*3") (pin "4") (pinfunction "4_4") (pintype "passive"))
      (node (ref "*4") (pin "1") (pinfunction "1_1") (pintype "passive"))
      (node (ref "*5") (pin "4") (pinfunction "4_4") (pintype "passive"))
      (node (ref "*6") (pin "1") (pinfunction "1_1") (pintype "passive"))
      (node (ref "*7") (pin "4") (pinfunction "4_4") (pintype "passive"))
      (node (ref "*8") (pin "1") (pinfunction "1_1") (pintype "passive"))
      (node (ref "C1") (pin "2") (pinfunction "2_2") (pintype "passive"))
      (node (ref "C12") (pin "1") (pinfunction "1_1") (pintype "passive"))
      (node (ref "C26") (pin "2") (pinfunction "2_2") (pintype "passive"))
      (node (ref "C27") (pin "2") (pinfunction "2_2") (pintype "passive"))
      (node (ref "C3") (pin "2") (pinfunction "2_2") (pintype "passive"))
      (node (ref "C32") (pin "2") (pinfunction "2_2") (pintype "passive"))
      (node (ref "C33") (pin "2") (pinfunction "2_2") (pintype "passive"))
      (node (ref "C34") (pin "2") (pinfunction "2_2") (pintype "passive"))
      (node (ref "C35") (pin "2") (pinfunction "2_2") (pintype "passive"))
      (node (ref "C49") (pin "2") (pinfunction "2_2") (pintype "passive"))
      (node (ref "C50") (pin "2") (pinfunction "2_2") (pintype "passive"))
      (node (ref "C57") (pin "2") (pinfunction "2_2") (pintype "passive"))
      (node (ref "C61") (pin "2") (pinfunction "2_2") (pintype "passive"))
      (node (ref "C65") (pin "2") (pinfunction "2_2") (pintype "passive"))
      (node (ref "C66") (pin "2") (pinfunction "2_2") (pintype "passive"))
      (node (ref "C73") (pin "2") (pinfunction "2_2") (pintype "passive"))
      (node (ref "C75") (pin "2") (pinfunction "2_2") (pintype "passive"))
      (node (ref "J12") (pin "4") (pinfunction "4_4") (pintype "passive"))
      (node (ref "J13") (pin "4") (pinfunction "4_4") (pintype "passive"))
      (node (ref "J5") (pin "4") (pinfunction "4_4") (pintype "passive"))
      (node (ref "J9") (pin "4") (pinfunction "4_4") (pintype "passive"))
      (node (ref "L5") (pin "2") (pinfunction "2_2") (pintype "passive"))
      (node (ref "TP10") (pin "1") (pinfunction "1_1") (pintype "passive"))
      (node (ref "U2") (pin "19") (pinfunction "AVDD_19") (pintype "power_in"))
      (node (ref "U2") (pin "21") (pinfunction "AVDD_21") (pintype "power_in"))
      (node (ref "U2") (pin "22") (pinfunction "AVDD_22") (pintype "power_in"))
      (node (ref "U2") (pin "54") (pinfunction "AVDD1_54") (pintype "power_in"))
      (node (ref "U2") (pin "56") (pinfunction "AVDD_56") (pintype "power_in"))
      (node (ref "U2") (pin "59") (pinfunction "AVDD_59") (pintype "power_in"))
      (node (ref "U3") (pin "8") (pinfunction "V+_8") (pintype "power_in"))
      (node (ref "U6") (pin "8") (pinfunction "V+_8") (pintype "power_in"))
      (node (ref "U7") (pin "8") (pinfunction "V+_8") (pintype "power_in"))
      (node (ref "U8") (pin "8") (pinfunction "V+_8") (pintype "power_in"))
      (node (ref "U9") (pin "8") (pinfunction "V+_8") (pintype "power_in"))
    )
    (net (code "2") (name "/+IN_A5") (class "Default")
      (node (ref "C55") (pin "2") (pinfunction "2_2") (pintype "passive"))
      (node (ref "Cn_5") (pin "2") (pinfunction "2_2") (pintype "passive"))
      (node (ref "D1_5") (pin "1") (pinfunction "A_1") (pintype "passive"))
      (node (ref "D2_5") (pin "3") (pinfunction "K_3") (pintype "passive"))
      (node (ref "J4") (pin "3") (pinfunction "3_3") (pintype "passive"))
      (node (ref "U6") (pin "3") (pinfunction "+IN_A_3") (pintype "input"))
    )
    (net (code "3") (name "/+IN_A6") (class "Default")
      (node (ref "C59") (pin "1") (pinfunction "1_1") (pintype "passive"))
      (node (ref "Cn") (pin "2") (pinfunction "2_2") (pintype "passive"))
      (node (ref "D1_6") (pin "1") (pinfunction "A_1") (pintype "passive"))
      (node (ref "D2_6") (pin "3") (pinfunction "K_3") (pintype "passive"))
      (node (ref "J10") (pin "3") (pinfunction "3_3") (pintype "passive"))
      (node (ref "U7") (pin "3") (pinfunction "+IN_A_3") (pintype "input"))
    )
    (net (code "4") (name "/+IN_B3") (class "Default")
      (node (ref "C3_3") (pin "1") (pinfunction "1_1") (pintype "passive"))
      (node (ref "J13") (pin "1") (pinfunction "1_1") (pintype "passive"))
      (node (ref "R3_3") (pin "2") (pinfunction "2_2") (pintype "passive"))
      (node (ref "U9") (pin "5") (pinfunction "+IN_B_5") (pintype "input"))
    )
    (net (code "5") (name "/+IN_B4") (class "Default")
      (node (ref "C3_4") (pin "1") (pinfunction "1_1") (pintype "passive"))
      (node (ref "J9") (pin "1") (pinfunction "1_1") (pintype "passive"))
      (node (ref "R3_4") (pin "2") (pinfunction "2_2") (pintype "passive"))
      (node (ref "U8") (pin "5") (pinfunction "+IN_B_5") (pintype "input"))
    )
    (net (code "6") (name "/+IN_B5") (class "Default")
      (node (ref "C56") (pin "1") (pinfunction "1_1") (pintype "passive"))
      (node (ref "J5") (pin "1") (pinfunction "1_1") (pintype "passive"))
      (node (ref "R23") (pin "2") (pinfunction "2_2") (pintype "passive"))
      (node (ref "U6") (pin "5") (pinfunction "+IN_B_5") (pintype "input"))
    )
    (net (code "7") (name "/+IN_B6") (class "Default")
      (node (ref "C60") (pin "1") (pinfunction "1_1") (pintype "passive"))
      (node (ref "J12") (pin "1") (pinfunction "1_1") (pintype "passive"))
      (node (ref "R25") (pin "2") (pinfunction "2_2") (pintype "passive"))
      (node (ref "U7") (pin "5") (pinfunction "+IN_B_5") (pintype "input"))
    )
    (net (code "8") (name "/-2.5V") (class "Default")
      (node (ref "*1") (pin "1") (pinfunction "1_1") (pintype "passive"))
      (node (ref "*2") (pin "4") (pinfunction "4_4") (pintype "passive"))
      (node (ref "*3") (pin "1") (pinfunction "1_1") (pintype "passive"))
      (node (ref "*4") (pin "4") (pinfunction "4_4") (pintype "passive"))
      (node (ref "*5") (pin "1") (pinfunction "1_1") (pintype "passive"))
      (node (ref "*6") (pin "4") (pinfunction "4_4") (pintype "passive"))
      (node (ref "*7") (pin "1") (pinfunction "1_1") (pintype "passive"))
      (node (ref "*8") (pin "4") (pinfunction "4_4") (pintype "passive"))
      (node (ref "C13") (pin "2") (pinfunction "2_2") (pintype "passive"))
      (node (ref "C2") (pin "2") (pinfunction "2_2") (pintype "passive"))
      (node (ref "C20") (pin "2") (pinfunction "2_2") (pintype "passive"))
      (node (ref "C21") (pin "1") (pinfunction "1_1") (pintype "passive"))
      (node (ref "C22") (pin "2") (pinfunction "2_2") (pintype "passive"))
      (node (ref "C23") (pin "1") (pinfunction "1_1") (pintype "passive"))
      (node (ref "C24") (pin "1") (pinfunction "1_1") (pintype "passive"))
      (node (ref "C25") (pin "1") (pinfunction "1_1") (pintype "passive"))
      (node (ref "C26") (pin "1") (pinfunction "1_1") (pintype "passive"))
      (node (ref "C27") (pin "1") (pinfunction "1_1") (pintype "passive"))
      (node (ref "C28") (pin "2") (pinfunction "2_2") (pintype "passive"))
      (node (ref "C29") (pin "2") (pinfunction "2_2") (pintype "passive"))
      (node (ref "C32") (pin "1") (pinfunction "1_1") (pintype "passive"))
      (node (ref "C33") (pin "1") (pinfunction "1_1") (pintype "passive"))
      (node (ref "C4") (pin "2") (pinfunction "2_2") (pintype "passive"))
      (node (ref "C45") (pin "2") (pinfunction "2_2") (pintype "passive"))
      (node (ref "C58") (pin "2") (pinfunction "2_2") (pintype "passive"))
      (node (ref "C62") (pin "2") (pinfunction "2_2") (pintype "passive"))
      (node (ref "C69") (pin "2") (pinfunction "2_2") (pintype "passive"))
      (node (ref "C70") (pin "2") (pinfunction "2_2") (pintype "passive"))
      (node (ref "C74") (pin "2") (pinfunction "2_2") (pintype "passive"))
      (node (ref "C79") (pin "2") (pinfunction "2_2") (pintype "passive"))
      (node (ref "J10") (pin "4") (pinfunction "4_4") (pintype "passive"))
      (node (ref "J11") (pin "4") (pinfunction "4_4") (pintype "passive"))
      (node (ref "J3") (pin "4") (pinfunction "4_4") (pintype "passive"))
      (node (ref "J4") (pin "4") (pinfunction "4_4") (pintype "passive"))
      (node (ref "L2") (pin "2") (pinfunction "2_2") (pintype "passive"))
      (node (ref "TP9") (pin "1") (pinfunction "1_1") (pintype "passive"))
      (node (ref "U2") (pin "20") (pinfunction "AVSS_20") (pintype "power_in"))
      (node (ref "U2") (pin "23") (pinfunction "AVSS_23") (pintype "power_in"))
      (node (ref "U2") (pin "25") (pinfunction "VREFN_25") (pintype "input"))
      (node (ref "U2") (pin "32") (pinfunction "AVSS_32") (pintype "power_in"))
      (node (ref "U2") (pin "53") (pinfunction "AVSS1_53") (pintype "power_in"))
      (node (ref "U2") (pin "57") (pinfunction "AVSS_57") (pintype "power_in"))
      (node (ref "U2") (pin "58") (pinfunction "AVSS_58") (pintype "power_in"))
      (node (ref "U3") (pin "4") (pinfunction "V-_4") (pintype "power_in"))
      (node (ref "U6") (pin "4") (pinfunction "V-_4") (pintype "power_in"))
      (node (ref "U7") (pin "4") (pinfunction "V-_4") (pintype "power_in"))
      (node (ref "U8") (pin "4") (pinfunction "V-_4") (pintype "power_in"))
      (node (ref "U9") (pin "4") (pinfunction "V-_4") (pintype "power_in"))
    )
    (net (code "9") (name "/-IN_B5") (class "Default")
      (node (ref "C56") (pin "2") (pinfunction "2_2") (pintype "passive"))
      (node (ref "R1_5") (pin "1") (pinfunction "1_1") (pintype "passive"))
      (node (ref "R24") (pin "2") (pinfunction "2_2") (pintype "passive"))
      (node (ref "R2_5") (pin "2") (pinfunction "2_2") (pintype "passive"))
      (node (ref "Rc_5") (pin "1") (pinfunction "1_1") (pintype "passive"))
      (node (ref "U6") (pin "2") (pinfunction "-IN_A_2") (pintype "input"))
    )
    (net (code "10") (name "/-IN_B6") (class "Default")
      (node (ref "C60") (pin "2") (pinfunction "2_2") (pintype "passive"))
      (node (ref "R1_6") (pin "1") (pinfunction "1_1") (pintype "passive"))
      (node (ref "R26") (pin "2") (pinfunction "2_2") (pintype "passive"))
      (node (ref "R2_6") (pin "2") (pinfunction "2_2") (pintype "passive"))
      (node (ref "Rc_6") (pin "1") (pinfunction "1_1") (pintype "passive"))
      (node (ref "U7") (pin "2") (pinfunction "-IN_A_2") (pintype "input"))
    )
    (net (code "11") (name "/BIAS") (class "Default")
      (node (ref "C14") (pin "2") (pinfunction "2_2") (pintype "passive"))
      (node (ref "R17") (pin "2") (pinfunction "2_2") (pintype "passive"))
      (node (ref "TP8") (pin "1") (pinfunction "1_1") (pintype "passive"))
      (node (ref "U2") (pin "62") (pinfunction "BIASIN_62") (pintype "input"))
      (node (ref "U2") (pin "63") (pinfunction "BIASOUT_63") (pintype "output"))
      (node (ref "U3") (pin "3") (pinfunction "INA+_3") (pintype "input"))
    )
    (net (code "12") (name "/CS") (class "Default")
      (node (ref "J2") (pin "4") (pinfunction "4_4") (pintype "passive"))
      (node (ref "M1") (pin "25") (pinfunction "P0.11_25") (pintype "passive"))
      (node (ref "R20") (pin "1") (pinfunction "1_1") (pintype "passive"))
      (node (ref "U2") (pin "39") (pinfunction "*CS_39") (pintype "input"))
    )
    (net (code "13") (name "/CS_1") (class "Default")
      (node (ref "J7") (pin "2") (pinfunction "CD/DAT3_2") (pintype "bidirectional"))
      (node (ref "M1") (pin "17") (pinfunction "P0.04_17") (pintype "passive"))
    )
    (net (code "14") (name "/DRDY") (class "Default")
      (node (ref "J1") (pin "2") (pinfunction "2_2") (pintype "passive"))
      (node (ref "M1") (pin "30") (pinfunction "P0.16_30") (pintype "passive"))
      (node (ref "U2") (pin "47") (pinfunction "*DRDY_47") (pintype "output"))
    )
    (net (code "15") (name "/DVDD") (class "Default")
      (node (ref "C15") (pin "2") (pinfunction "2_2") (pintype "passive"))
      (node (ref "C16") (pin "2") (pinfunction "2_2") (pintype "passive"))
      (node (ref "C30") (pin "2") (pinfunction "2_2") (pintype "passive"))
      (node (ref "C31") (pin "2") (pinfunction "2_2") (pintype "passive"))
      (node (ref "C39") (pin "2") (pinfunction "2_2") (pintype "passive"))
      (node (ref "C40") (pin "2") (pinfunction "2_2") (pintype "passive"))
      (node (ref "C46") (pin "2") (pinfunction "2_2") (pintype "passive"))
      (node (ref "C47") (pin "2") (pinfunction "2_2") (pintype "passive"))
      (node (ref "IC2") (pin "8") (pinfunction "V+_8") (pintype "passive"))
      (node (ref "IC4") (pin "1") (pinfunction "IN_1") (pintype "input"))
      (node (ref "IC4") (pin "3") (pinfunction "EN_3") (pintype "passive"))
      (node (ref "J7") (pin "4") (pinfunction "VDD_4") (pintype "power_in"))
      (node (ref "J8") (pin "1") (pinfunction "1_1") (pintype "passive"))
      (node (ref "M1") (pin "11") (pinfunction "VDD_11") (pintype "passive"))
      (node (ref "R15") (pin "2") (pinfunction "2_2") (pintype "passive"))
      (node (ref "R16") (pin "2") (pinfunction "2_2") (pintype "passive"))
      (node (ref "R19") (pin "2") (pinfunction "2_2") (pintype "passive"))
      (node (ref "R20") (pin "2") (pinfunction "2_2") (pintype "passive"))
      (node (ref "TP7") (pin "1") (pinfunction "1_1") (pintype "passive"))
      (node (ref "U2") (pin "48") (pinfunction "DVDD_48") (pintype "power_in"))
      (node (ref "U2") (pin "50") (pinfunction "DVDD_50") (pintype "power_in"))
      (node (ref "U2") (pin "52") (pinfunction "CLKSEL_52") (pintype "input"))
      (node (ref "U4") (pin "9") (pinfunction "VOUT_9") (pintype "output"))
    )
    (net (code "16") (name "/Elec_1") (class "Default")
      (node (ref "C5") (pin "2") (pinfunction "2_2") (pintype "passive"))
      (node (ref "R5") (pin "2") (pinfunction "2_2") (pintype "passive"))
      (node (ref "U2") (pin "16") (pinfunction "IN1P_16") (pintype "input"))
    )
    (net (code "17") (name "/Elec_2") (class "Default")
      (node (ref "C6") (pin "2") (pinfunction "2_2") (pintype "passive"))
      (node (ref "R6") (pin "2") (pinfunction "2_2") (pintype "passive"))
      (node (ref "U2") (pin "15") (pinfunction "IN1N_15") (pintype "input"))
    )
    (net (code "18") (name "/Elec_3") (class "Default")
      (node (ref "*7") (pin "3") (pinfunction "3_3") (pintype "passive"))
      (node (ref "*8") (pin "2") (pinfunction "2_2") (pintype "passive"))
      (node (ref "C7") (pin "2") (pinfunction "2_2") (pintype "passive"))
      (node (ref "R7") (pin "2") (pinfunction "2_2") (pintype "passive"))
      (node (ref "U2") (pin "14") (pinfunction "IN2P_14") (pintype "input"))
    )
    (net (code "19") (name "/Elec_4") (class "Default")
      (node (ref "*5") (pin "3") (pinfunction "3_3") (pintype "passive"))
      (node (ref "*6") (pin "2") (pinfunction "2_2") (pintype "passive"))
      (node (ref "C8") (pin "2") (pinfunction "2_2") (pintype "passive"))
      (node (ref "R8") (pin "2") (pinfunction "2_2") (pintype "passive"))
      (node (ref "U2") (pin "13") (pinfunction "IN2N_13") (pintype "input"))
    )
    (net (code "20") (name "/Elec_5") (class "Default")
      (node (ref "*3") (pin "3") (pinfunction "3_3") (pintype "passive"))
      (node (ref "*4") (pin "2") (pinfunction "2_2") (pintype "passive"))
      (node (ref "C63") (pin "2") (pinfunction "2_2") (pintype "passive"))
      (node (ref "R27") (pin "2") (pinfunction "2_2") (pintype "passive"))
      (node (ref "U2") (pin "12") (pinfunction "IN3P_12") (pintype "input"))
    )
    (net (code "21") (name "/Elec_6") (class "Default")
      (node (ref "*1") (pin "3") (pinfunction "3_3") (pintype "passive"))
      (node (ref "*2") (pin "2") (pinfunction "2_2") (pintype "passive"))
      (node (ref "C64") (pin "2") (pinfunction "2_2") (pintype "passive"))
      (node (ref "R28") (pin "2") (pinfunction "2_2") (pintype "passive"))
      (node (ref "U2") (pin "11") (pinfunction "IN3N_11") (pintype "input"))
    )
    (net (code "22") (name "/GUARD_3") (class "Default")
      (node (ref "J11") (pin "2") (pinfunction "2_2") (pintype "passive"))
      (node (ref "R1_3") (pin "1") (pinfunction "1_1") (pintype "passive"))
      (node (ref "R2_3") (pin "2") (pinfunction "2_2") (pintype "passive"))
      (node (ref "Rc_3") (pin "1") (pinfunction "1_1") (pintype "passive"))
      (node (ref "U9") (pin "2") (pinfunction "-IN_A_2") (pintype "input"))
    )
    (net (code "23") (name "/GUARD_4") (class "Default")
      (node (ref "J3") (pin "2") (pinfunction "2_2") (pintype "passive"))
      (node (ref "R1_4") (pin "1") (pinfunction "1_1") (pintype "passive"))
      (node (ref "R2_4") (pin "2") (pinfunction "2_2") (pintype "passive"))
      (node (ref "Rc_4") (pin "1") (pinfunction "1_1") (pintype "passive"))
      (node (ref "U8") (pin "2") (pinfunction "-IN_A_2") (pintype "input"))
    )
    (net (code "24") (name "/GUARD_5") (class "Default")
      (node (ref "R24") (pin "1") (pinfunction "1_1") (pintype "passive"))
    )
    (net (code "25") (name "/GUARD_6") (class "Default")
      (node (ref "R26") (pin "1") (pinfunction "1_1") (pintype "passive"))
    )
    (net (code "26") (name "/MISO") (class "Default")
      (node (ref "J2") (pin "2") (pinfunction "2_2") (pintype "passive"))
      (node (ref "J7") (pin "7") (pinfunction "DAT0_7") (pintype "bidirectional"))
      (node (ref "M1") (pin "26") (pinfunction "P0.12_26") (pintype "passive"))
      (node (ref "U2") (pin "43") (pinfunction "DOUT_43") (pintype "output"))
    )
    (net (code "27") (name "/MOSI") (class "Default")
      (node (ref "J2") (pin "1") (pinfunction "1_1") (pintype "passive"))
      (node (ref "J7") (pin "3") (pinfunction "CMD_3") (pintype "bidirectional"))
      (node (ref "M1") (pin "27") (pinfunction "P0.13_27") (pintype "passive"))
      (node (ref "U2") (pin "34") (pinfunction "DIN_34") (pintype "input"))
    )
    (net (code "28") (name "/OUT_A3") (class "Default")
      (node (ref "C3_3") (pin "2") (pinfunction "2_2") (pintype "passive"))
      (node (ref "J11") (pin "1") (pinfunction "1_1") (pintype "passive"))
      (node (ref "R1_3") (pin "2") (pinfunction "2_2") (pintype "passive"))
      (node (ref "Rn1_3") (pin "2") (pinfunction "2_2") (pintype "passive"))
      (node (ref "Rn_3") (pin "1") (pinfunction "1_1") (pintype "passive"))
      (node (ref "U9") (pin "1") (pinfunction "OUT_A_1") (pintype "output"))
    )
    (net (code "29") (name "/OUT_A4") (class "Default")
      (node (ref "C3_4") (pin "2") (pinfunction "2_2") (pintype "passive"))
      (node (ref "J3") (pin "1") (pinfunction "1_1") (pintype "passive"))
      (node (ref "R1_4") (pin "2") (pinfunction "2_2") (pintype "passive"))
      (node (ref "Rn1_4") (pin "2") (pinfunction "2_2") (pintype "passive"))
      (node (ref "Rn_4") (pin "1") (pinfunction "1_1") (pintype "passive"))
      (node (ref "U8") (pin "1") (pinfunction "OUT_A_1") (pintype "output"))
    )
    (net (code "30") (name "/OUT_A5") (class "Default")
      (node (ref "J4") (pin "1") (pinfunction "1_1") (pintype "passive"))
      (node (ref "J4") (pin "2") (pinfunction "2_2") (pintype "passive"))
      (node (ref "R1_5") (pin "2") (pinfunction "2_2") (pintype "passive"))
      (node (ref "Rn1_5") (pin "2") (pinfunction "2_2") (pintype "passive"))
      (node (ref "U6") (pin "1") (pinfunction "OUT_A_1") (pintype "output"))
    )
    (net (code "31") (name "/OUT_A6") (class "Default")
      (node (ref "J10") (pin "1") (pinfunction "1_1") (pintype "passive"))
      (node (ref "J10") (pin "2") (pinfunction "2_2") (pintype "passive"))
      (node (ref "R1_6") (pin "2") (pinfunction "2_2") (pintype "passive"))
      (node (ref "Rn1") (pin "2") (pinfunction "2_2") (pintype "passive"))
      (node (ref "U7") (pin "1") (pinfunction "OUT_A_1") (pintype "output"))
    )
    (net (code "32") (name "/PWDN") (class "Default")
      (node (ref "J1") (pin "4") (pinfunction "4_4") (pintype "passive"))
      (node (ref "M1") (pin "34") (pinfunction "P0.20_34") (pintype "passive"))
      (node (ref "R19") (pin "1") (pinfunction "1_1") (pintype "passive"))
      (node (ref "U2") (pin "35") (pinfunction "*PWDN_35") (pintype "power_in"))
    )
    (net (code "33") (name "/REF_IN") (class "Default")
      (node (ref "TP6") (pin "1") (pinfunction "1_1") (pintype "passive"))
      (node (ref "U3") (pin "5") (pinfunction "INB+_5") (pintype "input"))
    )
    (net (code "34") (name "/RESET") (class "Default")
      (node (ref "J1") (pin "3") (pinfunction "3_3") (pintype "passive"))
      (node (ref "M1") (pin "29") (pinfunction "P0.15_29") (pintype "passive"))
      (node (ref "U2") (pin "36") (pinfunction "*RESET_36") (pintype "input"))
    )
    (net (code "35") (name "/SCK") (class "Default")
      (node (ref "J2") (pin "3") (pinfunction "3_3") (pintype "passive"))
      (node (ref "M1") (pin "28") (pinfunction "P0.14_28") (pintype "passive"))
      (node (ref "U2") (pin "40") (pinfunction "SCLK_40") (pintype "input"))
    )
    (net (code "36") (name "/START") (class "Default")
      (node (ref "J1") (pin "1") (pinfunction "1_1") (pintype "passive"))
      (node (ref "M1") (pin "38") (pinfunction "P0.22_38") (pintype "passive"))
      (node (ref "U2") (pin "38") (pinfunction "START_38") (pintype "input"))
    )
    (net (code "37") (name "/SWDIO") (class "Default")
      (node (ref "J8") (pin "2") (pinfunction "2_2") (pintype "passive"))
      (node (ref "M1") (pin "37") (pinfunction "SWDIO_37") (pintype "passive"))
    )
    (net (code "38") (name "/SWD_CLK") (class "Default")
      (node (ref "J7") (pin "5") (pinfunction "CLK_5") (pintype "input"))
      (node (ref "J8") (pin "3") (pinfunction "3_3") (pintype "passive"))
      (node (ref "M1") (pin "36") (pinfunction "SWDCLK_36") (pintype "passive"))
    )
    (net (code "39") (name "/Signal_1") (class "Default")
      (node (ref "R5") (pin "1") (pinfunction "1_1") (pintype "passive"))
      (node (ref "TP1") (pin "1") (pinfunction "1_1") (pintype "passive"))
      (node (ref "TP2") (pin "1") (pinfunction "1_1") (pintype "passive"))
    )
    (net (code "40") (name "/Signal_2") (class "Default")
      (node (ref "R6") (pin "1") (pinfunction "1_1") (pintype "passive"))
      (node (ref "TP3") (pin "1") (pinfunction "1_1") (pintype "passive"))
      (node (ref "TP4") (pin "1") (pinfunction "1_1") (pintype "passive"))
    )
    (net (code "41") (name "/Signal_3") (class "Default")
      (node (ref "C_test3") (pin "1") (pinfunction "1_1") (pintype "passive"))
      (node (ref "Cn_3") (pin "2") (pinfunction "2_2") (pintype "passive"))
      (node (ref "Cn_3a") (pin "1") (pinfunction "1_1") (pintype "passive"))
      (node (ref "D1_3") (pin "1") (pinfunction "A_1") (pintype "passive"))
      (node (ref "D2_3") (pin "3") (pinfunction "K_3") (pintype "passive"))
      (node (ref "J11") (pin "3") (pinfunction "3_3") (pintype "passive"))
      (node (ref "U9") (pin "3") (pinfunction "+IN_A_3") (pintype "input"))
    )
    (net (code "42") (name "/Signal_3_1") (class "Default")
      (node (ref "J13") (pin "2") (pinfunction "2_2") (pintype "passive"))
      (node (ref "J13") (pin "3") (pinfunction "3_3") (pintype "passive"))
      (node (ref "R7") (pin "1") (pinfunction "1_1") (pintype "passive"))
      (node (ref "U9") (pin "6") (pinfunction "-IN_B_6") (pintype "input"))
      (node (ref "U9") (pin "7") (pinfunction "OUT_B_7") (pintype "output"))
    )
    (net (code "43") (name "/Signal_4") (class "Default")
      (node (ref "C_test4") (pin "1") (pinfunction "1_1") (pintype "passive"))
      (node (ref "Cn_4") (pin "2") (pinfunction "2_2") (pintype "passive"))
      (node (ref "Cn_4a") (pin "1") (pinfunction "1_1") (pintype "passive"))
      (node (ref "D1_4") (pin "1") (pinfunction "A_1") (pintype "passive"))
      (node (ref "D2_4") (pin "3") (pinfunction "K_3") (pintype "passive"))
      (node (ref "J3") (pin "3") (pinfunction "3_3") (pintype "passive"))
      (node (ref "U8") (pin "3") (pinfunction "+IN_A_3") (pintype "input"))
    )
    (net (code "44") (name "/Signal_4_1") (class "Default")
      (node (ref "J9") (pin "2") (pinfunction "2_2") (pintype "passive"))
      (node (ref "J9") (pin "3") (pinfunction "3_3") (pintype "passive"))
      (node (ref "R8") (pin "1") (pinfunction "1_1") (pintype "passive"))
      (node (ref "U8") (pin "6") (pinfunction "-IN_B_6") (pintype "input"))
      (node (ref "U8") (pin "7") (pinfunction "OUT_B_7") (pintype "output"))
    )
    (net (code "45") (name "/Signal_5") (class "Default")
      (node (ref "C55") (pin "1") (pinfunction "1_1") (pintype "passive"))
      (node (ref "C_test5") (pin "2") (pinfunction "2_2") (pintype "passive"))
    )
    (net (code "46") (name "/Signal_5_1") (class "Default")
      (node (ref "J5") (pin "2") (pinfunction "2_2") (pintype "passive"))
      (node (ref "J5") (pin "3") (pinfunction "3_3") (pintype "passive"))
      (node (ref "R27") (pin "1") (pinfunction "1_1") (pintype "passive"))
      (node (ref "U6") (pin "6") (pinfunction "-IN_B_6") (pintype "input"))
      (node (ref "U6") (pin "7") (pinfunction "OUT_B_7") (pintype "output"))
    )
    (net (code "47") (name "/Signal_6") (class "Default")
      (node (ref "C59") (pin "2") (pinfunction "2_2") (pintype "passive"))
      (node (ref "C_test6") (pin "2") (pinfunction "2_2") (pintype "passive"))
    )
    (net (code "48") (name "/Signal_6_1") (class "Default")
      (node (ref "J12") (pin "2") (pinfunction "2_2") (pintype "passive"))
      (node (ref "J12") (pin "3") (pinfunction "3_3") (pintype "passive"))
      (node (ref "R28") (pin "1") (pinfunction "1_1") (pintype "passive"))
      (node (ref "U7") (pin "6") (pinfunction "-IN_B_6") (pintype "input"))
      (node (ref "U7") (pin "7") (pinfunction "OUT_B_7") (pintype "output"))
    )
    (net (code "49") (name "/VCC") (class "Default")
      (node (ref "C17") (pin "2") (pinfunction "2_2") (pintype "passive"))
      (node (ref "S1") (pin "3") (pinfunction "ON_2_3") (pintype "passive"))
      (node (ref "U4") (pin "2") (pinfunction "VIN_2") (pintype "input"))
      (node (ref "U4") (pin "3") (pinfunction "EN_3") (pintype "input"))
    )
    (net (code "50") (name "GND") (class "Default")
      (node (ref "*1") (pin "2") (pinfunction "2_2") (pintype "passive"))
      (node (ref "*2") (pin "3") (pinfunction "3_3") (pintype "passive"))
      (node (ref "*3") (pin "2") (pinfunction "2_2") (pintype "passive"))
      (node (ref "*4") (pin "3") (pinfunction "3_3") (pintype "passive"))
      (node (ref "*5") (pin "2") (pinfunction "2_2") (pintype "passive"))
      (node (ref "*6") (pin "3") (pinfunction "3_3") (pintype "passive"))
      (node (ref "*7") (pin "2") (pinfunction "2_2") (pintype "passive"))
      (node (ref "*8") (pin "3") (pinfunction "3_3") (pintype "passive"))
      (node (ref "C1") (pin "1") (pinfunction "1_1") (pintype "passive"))
      (node (ref "C10") (pin "1") (pinfunction "1_1") (pintype "passive"))
      (node (ref "C11") (pin "1") (pinfunction "1_1") (pintype "passive"))
      (node (ref "C12") (pin "2") (pinfunction "2_2") (pintype "passive"))
      (node (ref "C13") (pin "1") (pinfunction "1_1") (pintype "passive"))
      (node (ref "C15") (pin "1") (pinfunction "1_1") (pintype "passive"))
      (node (ref "C16") (pin "1") (pinfunction "1_1") (pintype "passive"))
      (node (ref "C17") (pin "1") (pinfunction "1_1") (pintype "passive"))
      (node (ref "C18") (pin "1") (pinfunction "1_1") (pintype "passive"))
      (node (ref "C19") (pin "1") (pinfunction "1_1") (pintype "passive"))
      (node (ref "C1_3") (pin "2") (pinfunction "2_2") (pintype "passive"))
      (node (ref "C1_4") (pin "2") (pinfunction "2_2") (pintype "passive"))
      (node (ref "C1_5") (pin "2") (pinfunction "2_2") (pintype "passive"))
      (node (ref "C1_6") (pin "2") (pinfunction "2_2") (pintype "passive"))
      (node (ref "C2") (pin "1") (pinfunction "1_1") (pintype "passive"))
      (node (ref "C28") (pin "1") (pinfunction "1_1") (pintype "passive"))
      (node (ref "C29") (pin "1") (pinfunction "1_1") (pintype "passive"))
      (node (ref "C3") (pin "1") (pinfunction "1_1") (pintype "passive"))
      (node (ref "C30") (pin "1") (pinfunction "1_1") (pintype "passive"))
      (node (ref "C31") (pin "1") (pinfunction "1_1") (pintype "passive"))
      (node (ref "C34") (pin "1") (pinfunction "1_1") (pintype "passive"))
      (node (ref "C35") (pin "1") (pinfunction "1_1") (pintype "passive"))
      (node (ref "C37") (pin "2") (pinfunction "2_2") (pintype "passive"))
      (node (ref "C38") (pin "1") (pinfunction "1_1") (pintype "passive"))
      (node (ref "C39") (pin "1") (pinfunction "1_1") (pintype "passive"))
      (node (ref "C4") (pin "1") (pinfunction "1_1") (pintype "passive"))
      (node (ref "C40") (pin "1") (pinfunction "1_1") (pintype "passive"))
      (node (ref "C41") (pin "1") (pinfunction "1_1") (pintype "passive"))
      (node (ref "C42") (pin "1") (pinfunction "1_1") (pintype "passive"))
      (node (ref "C43") (pin "1") (pinfunction "1_1") (pintype "passive"))
      (node (ref "C44") (pin "1") (pinfunction "1_1") (pintype "passive"))
      (node (ref "C45") (pin "1") (pinfunction "1_1") (pintype "passive"))
      (node (ref "C46") (pin "1") (pinfunction "1_1") (pintype "passive"))
      (node (ref "C47") (pin "1") (pinfunction "1_1") (pintype "passive"))
      (node (ref "C48") (pin "1") (pinfunction "1_1") (pintype "passive"))
      (node (ref "C49") (pin "1") (pinfunction "1_1") (pintype "passive"))
      (node (ref "C5") (pin "1") (pinfunction "1_1") (pintype "passive"))
      (node (ref "C50") (pin "1") (pinfunction "1_1") (pintype "passive"))
      (node (ref "C51") (pin "1") (pinfunction "1_1") (pintype "passive"))
      (node (ref "C53") (pin "1") (pinfunction "1_1") (pintype "passive"))
      (node (ref "C54") (pin "1") (pinfunction "1_1") (pintype "passive"))
      (node (ref "C57") (pin "1") (pinfunction "1_1") (pintype "passive"))
      (node (ref "C58") (pin "1") (pinfunction "1_1") (pintype "passive"))
      (node (ref "C6") (pin "1") (pinfunction "1_1") (pintype "passive"))
      (node (ref "C61") (pin "1") (pinfunction "1_1") (pintype "passive"))
      (node (ref "C62") (pin "1") (pinfunction "1_1") (pintype "passive"))
      (node (ref "C63") (pin "1") (pinfunction "1_1") (pintype "passive"))
      (node (ref "C64") (pin "1") (pinfunction "1_1") (pintype "passive"))
      (node (ref "C65") (pin "1") (pinfunction "1_1") (pintype "passive"))
      (node (ref "C66") (pin "1") (pinfunction "1_1") (pintype "passive"))
      (node (ref "C69") (pin "1") (pinfunction "1_1") (pintype "passive"))
      (node (ref "C7") (pin "1") (pinfunction "1_1") (pintype "passive"))
      (node (ref "C70") (pin "1") (pinfunction "1_1") (pintype "passive"))
      (node (ref "C73") (pin "1") (pinfunction "1_1") (pintype "passive"))
      (node (ref "C74") (pin "1") (pinfunction "1_1") (pintype "passive"))
      (node (ref "C75") (pin "1") (pinfunction "1_1") (pintype "passive"))
      (node (ref "C79") (pin "1") (pinfunction "1_1") (pintype "passive"))
      (node (ref "C8") (pin "1") (pinfunction "1_1") (pintype "passive"))
      (node (ref "C9") (pin "1") (pinfunction "1_1") (pintype "passive"))
      (node (ref "H1") (pin "4") (pinfunction "ID_4") (pintype "passive"))
      (node (ref "H1") (pin "5") (pinfunction "GND_5") (pintype "passive"))
      (node (ref "IC2") (pin "3") (pinfunction "GND_3") (pintype "passive"))
      (node (ref "IC3") (pin "1") (pinfunction "GND_1") (pintype "passive"))
      (node (ref "IC4") (pin "2") (pinfunction "GND_2") (pintype "power_in"))
      (node (ref "J6") (pin "2") (pinfunction "2_2") (pintype "passive"))
      (node (ref "J7") (pin "6") (pinfunction "VSS_6") (pintype "power_in"))
      (node (ref "J7") (pin "DL") (pinfunction "DET_LEVEL_DL") (pintype "passive"))
      (node (ref "J7") (pin "DS") (pinfunction "DET_SWT_DS") (pintype "passive"))
      (node (ref "J8") (pin "4") (pinfunction "4_4") (pintype "passive"))
      (node (ref "LED2") (pin "K") (pinfunction "K_K") (pintype "passive"))
      (node (ref "LED3") (pin "K") (pinfunction "K_K") (pintype "passive"))
      (node (ref "M1") (pin "1") (pinfunction "GND_1") (pintype "passive"))
      (node (ref "M1") (pin "12") (pinfunction "GND_12") (pintype "passive"))
      (node (ref "M1") (pin "24") (pinfunction "GND_24") (pintype "passive"))
      (node (ref "M1") (pin "39") (pinfunction "GND_39") (pintype "passive"))
      (node (ref "R11") (pin "2") (pinfunction "2_2") (pintype "passive"))
      (node (ref "R12") (pin "2") (pinfunction "2_2") (pintype "passive"))
      (node (ref "R13") (pin "2") (pinfunction "2_2") (pintype "passive"))
      (node (ref "R14") (pin "2") (pinfunction "2_2") (pintype "passive"))
      (node (ref "R18") (pin "1") (pinfunction "1_1") (pintype "passive"))
      (node (ref "R2") (pin "1") (pinfunction "1_1") (pintype "passive"))
      (node (ref "R23") (pin "1") (pinfunction "1_1") (pintype "passive"))
      (node (ref "R25") (pin "1") (pinfunction "1_1") (pintype "passive"))
      (node (ref "R29") (pin "2") (pinfunction "2_2") (pintype "passive"))
      (node (ref "R3_3") (pin "1") (pinfunction "1_1") (pintype "passive"))
      (node (ref "R3_4") (pin "1") (pinfunction "1_1") (pintype "passive"))
      (node (ref "R9") (pin "2") (pinfunction "2_2") (pintype "passive"))
      (node (ref "Rb_3") (pin "1") (pinfunction "1_1") (pintype "passive"))
      (node (ref "Rb_4") (pin "1") (pinfunction "1_1") (pintype "passive"))
      (node (ref "Rb_5") (pin "1") (pinfunction "1_1") (pintype "passive"))
      (node (ref "Rb_6") (pin "1") (pinfunction "1_1") (pintype "passive"))
      (node (ref "Rn2") (pin "1") (pinfunction "1_1") (pintype "passive"))
      (node (ref "Rn2_3") (pin "1") (pinfunction "1_1") (pintype "passive"))
      (node (ref "Rn2_4") (pin "1") (pinfunction "1_1") (pintype "passive"))
      (node (ref "Rn2_5") (pin "1") (pinfunction "1_1") (pintype "passive"))
      (node (ref "Rn_3") (pin "3") (pinfunction "3_3") (pintype "passive"))
      (node (ref "Rn_4") (pin "3") (pinfunction "3_3") (pintype "passive"))
      (node (ref "U1") (pin "2") (pinfunction "VSS_2") (pintype "power_in"))
      (node (ref "U2") (pin "31") (pinfunction "RESV1_31") (pintype "input"))
      (node (ref "U2") (pin "33") (pinfunction "DGND_33") (pintype "power_in"))
      (node (ref "U2") (pin "41") (pinfunction "DAISY_IN_41") (pintype "input"))
      (node (ref "U2") (pin "49") (pinfunction "DGND_49") (pintype "power_in"))
      (node (ref "U2") (pin "51") (pinfunction "DGND_51") (pintype "power_in"))
      (node (ref "U4") (pin "11") (pinfunction "EPAD_11") (pintype "passive"))
      (node (ref "U4") (pin "4") (pinfunction "PS/SYNC_4") (pintype "input"))
      (node (ref "U4") (pin "7") (pinfunction "GND_7") (pintype "power_in"))
    )
    (net (code "51") (name "Net-(C1_3-Pad1)") (class "Default")
      (node (ref "C1_3") (pin "1") (pinfunction "1_1") (pintype "passive"))
      (node (ref "R2_3") (pin "1") (pinfunction "1_1") (pintype "passive"))
    )
    (net (code "52") (name "Net-(C1_4-Pad1)") (class "Default")
      (node (ref "C1_4") (pin "1") (pinfunction "1_1") (pintype "passive"))
      (node (ref "R2_4") (pin "1") (pinfunction "1_1") (pintype "passive"))
    )
    (net (code "53") (name "Net-(C1_5-Pad1)") (class "Default")
      (node (ref "C1_5") (pin "1") (pinfunction "1_1") (pintype "passive"))
      (node (ref "R2_5") (pin "1") (pinfunction "1_1") (pintype "passive"))
    )
    (net (code "54") (name "Net-(C1_6-Pad1)") (class "Default")
      (node (ref "C1_6") (pin "1") (pinfunction "1_1") (pintype "passive"))
      (node (ref "R2_6") (pin "1") (pinfunction "1_1") (pintype "passive"))
    )
    (net (code "55") (name "Net-(Cn-Pad1)") (class "Default")
      (node (ref "Cn") (pin "1") (pinfunction "1_1") (pintype "passive"))
      (node (ref "Rn1") (pin "1") (pinfunction "1_1") (pintype "passive"))
      (node (ref "Rn2") (pin "2") (pinfunction "2_2") (pintype "passive"))
    )
    (net (code "56") (name "Net-(Cn_3-Pad1)") (class "Default")
      (node (ref "Cn_3") (pin "1") (pinfunction "1_1") (pintype "passive"))
      (node (ref "Cn_3a") (pin "2") (pinfunction "2_2") (pintype "passive"))
      (node (ref "Rn1_3") (pin "1") (pinfunction "1_1") (pintype "passive"))
      (node (ref "Rn2_3") (pin "2") (pinfunction "2_2") (pintype "passive"))
      (node (ref "Rn_3") (pin "2") (pinfunction "2_2") (pintype "passive"))
    )
    (net (code "57") (name "Net-(Cn_4-Pad1)") (class "Default")
      (node (ref "Cn_4") (pin "1") (pinfunction "1_1") (pintype "passive"))
      (node (ref "Cn_4a") (pin "2") (pinfunction "2_2") (pintype "passive"))
      (node (ref "Rn1_4") (pin "1") (pinfunction "1_1") (pintype "passive"))
      (node (ref "Rn2_4") (pin "2") (pinfunction "2_2") (pintype "passive"))
      (node (ref "Rn_4") (pin "2") (pinfunction "2_2") (pintype "passive"))
    )
    (net (code "58") (name "Net-(Cn_5-Pad1)") (class "Default")
      (node (ref "Cn_5") (pin "1") (pinfunction "1_1") (pintype "passive"))
      (node (ref "Rn1_5") (pin "1") (pinfunction "1_1") (pintype "passive"))
      (node (ref "Rn2_5") (pin "2") (pinfunction "2_2") (pintype "passive"))
    )
    (net (code "59") (name "Net-(D1-A)") (class "Default")
      (node (ref "C11") (pin "2") (pinfunction "2_2") (pintype "passive"))
      (node (ref "D1") (pin "2") (pinfunction "A_2") (pintype "passive"))
      (node (ref "J6") (pin "1") (pinfunction "1_1") (pintype "passive"))
      (node (ref "U1") (pin "3") (pinfunction "VBAT_3") (pintype "power_in"))
    )
    (net (code "60") (name "Net-(D1-K)") (class "Default")
      (node (ref "D1") (pin "1") (pinfunction "K_1") (pintype "passive"))
      (node (ref "S1") (pin "2") (pinfunction "COM_2") (pintype "passive"))
    )
    (net (code "61") (name "Net-(D1_3-K)") (class "Default")
      (node (ref "D1_3") (pin "3") (pinfunction "K_3") (pintype "passive"))
      (node (ref "D2_3") (pin "1") (pinfunction "A_1") (pintype "passive"))
      (node (ref "Rb_3") (pin "2") (pinfunction "2_2") (pintype "passive"))
      (node (ref "Rc_3") (pin "2") (pinfunction "2_2") (pintype "passive"))
    )
    (net (code "62") (name "Net-(D1_4-K)") (class "Default")
      (node (ref "D1_4") (pin "3") (pinfunction "K_3") (pintype "passive"))
      (node (ref "D2_4") (pin "1") (pinfunction "A_1") (pintype "passive"))
      (node (ref "Rb_4") (pin "2") (pinfunction "2_2") (pintype "passive"))
      (node (ref "Rc_4") (pin "2") (pinfunction "2_2") (pintype "passive"))
    )
    (net (code "63") (name "Net-(D1_5-K)") (class "Default")
      (node (ref "D1_5") (pin "3") (pinfunction "K_3") (pintype "passive"))
      (node (ref "D2_5") (pin "1") (pinfunction "A_1") (pintype "passive"))
      (node (ref "Rb_5") (pin "2") (pinfunction "2_2") (pintype "passive"))
      (node (ref "Rc_5") (pin "2") (pinfunction "2_2") (pintype "passive"))
    )
    (net (code "64") (name "Net-(D1_6-K)") (class "Default")
      (node (ref "D1_6") (pin "3") (pinfunction "K_3") (pintype "passive"))
      (node (ref "D2_6") (pin "1") (pinfunction "A_1") (pintype "passive"))
      (node (ref "Rb_6") (pin "2") (pinfunction "2_2") (pintype "passive"))
      (node (ref "Rc_6") (pin "2") (pinfunction "2_2") (pintype "passive"))
    )
    (net (code "65") (name "Net-(D2-A)") (class "Default")
      (node (ref "D2") (pin "2") (pinfunction "A_2") (pintype "passive"))
      (node (ref "H1") (pin "1") (pinfunction "VCC_1") (pintype "passive"))
    )
    (net (code "66") (name "Net-(D2-K)") (class "Default")
      (node (ref "C10") (pin "2") (pinfunction "2_2") (pintype "passive"))
      (node (ref "C9") (pin "2") (pinfunction "2_2") (pintype "passive"))
      (node (ref "D2") (pin "1") (pinfunction "K_1") (pintype "passive"))
      (node (ref "LED1") (pin "1") (pinfunction "1_1") (pintype "passive"))
      (node (ref "U1") (pin "4") (pinfunction "VDD_4") (pintype "power_in"))
    )
    (net (code "67") (name "Net-(IC2-CAP+)") (class "Default")
      (node (ref "C36") (pin "1") (pinfunction "1_1") (pintype "passive"))
      (node (ref "IC2") (pin "2") (pinfunction "CAP+_2") (pintype "passive"))
    )
    (net (code "68") (name "Net-(IC2-CAP-)") (class "Default")
      (node (ref "C36") (pin "2") (pinfunction "2_2") (pintype "passive"))
      (node (ref "IC2") (pin "4") (pinfunction "CAP-_4") (pintype "passive"))
    )
    (net (code "69") (name "Net-(IC2-OUT)") (class "Default")
      (node (ref "C41") (pin "2") (pinfunction "2_2") (pintype "passive"))
      (node (ref "C42") (pin "2") (pinfunction "2_2") (pintype "passive"))
      (node (ref "IC2") (pin "5") (pinfunction "OUT_5") (pintype "passive"))
      (node (ref "IC3") (pin "2") (pinfunction "IN_2") (pintype "passive"))
      (node (ref "IC3") (pin "3") (pinfunction "EN_3") (pintype "passive"))
    )
    (net (code "70") (name "Net-(IC3-NR{slash}FB)") (class "Default")
      (node (ref "C37") (pin "1") (pinfunction "1_1") (pintype "passive"))
      (node (ref "IC3") (pin "4") (pinfunction "NR/FB_4") (pintype "passive"))
      (node (ref "R1") (pin "1") (pinfunction "1_1") (pintype "passive"))
      (node (ref "R2") (pin "2") (pinfunction "2_2") (pintype "passive"))
    )
    (net (code "71") (name "Net-(IC3-OUT)") (class "Default")
      (node (ref "C43") (pin "2") (pinfunction "2_2") (pintype "passive"))
      (node (ref "C44") (pin "2") (pinfunction "2_2") (pintype "passive"))
      (node (ref "IC3") (pin "5") (pinfunction "OUT_5") (pintype "passive"))
      (node (ref "L2") (pin "1") (pinfunction "1_1") (pintype "passive"))
      (node (ref "R1") (pin "2") (pinfunction "2_2") (pintype "passive"))
    )
    (net (code "72") (name "Net-(IC4-BYP)") (class "Default")
      (node (ref "C51") (pin "2") (pinfunction "2_2") (pintype "passive"))
      (node (ref "IC4") (pin "4") (pinfunction "BYP_4") (pintype "passive"))
    )
    (net (code "73") (name "Net-(IC4-OUT)") (class "Default")
      (node (ref "C48") (pin "2") (pinfunction "2_2") (pintype "passive"))
      (node (ref "IC4") (pin "5") (pinfunction "OUT_5") (pintype "output"))
      (node (ref "L5") (pin "1") (pinfunction "1_1") (pintype "passive"))
    )
    (net (code "74") (name "Net-(L3-Pad1)") (class "Default")
      (node (ref "L3") (pin "1") (pinfunction "1_1") (pintype "passive"))
      (node (ref "L4") (pin "2") (pinfunction "2_2") (pintype "passive"))
    )
    (net (code "75") (name "Net-(LED1-Pad2)") (class "Default")
      (node (ref "LED1") (pin "2") (pinfunction "2_2") (pintype "passive"))
      (node (ref "R10") (pin "1") (pinfunction "1_1") (pintype "passive"))
    )
    (net (code "76") (name "Net-(LED2-PadA)") (class "Default")
      (node (ref "LED2") (pin "A") (pinfunction "A_A") (pintype "passive"))
      (node (ref "R21") (pin "2") (pinfunction "2_2") (pintype "passive"))
    )
    (net (code "77") (name "Net-(LED3-PadA)") (class "Default")
      (node (ref "LED3") (pin "A") (pinfunction "A_A") (pintype "passive"))
      (node (ref "R22") (pin "2") (pinfunction "2_2") (pintype "passive"))
    )
    (net (code "78") (name "Net-(M1-DCC)") (class "Default")
      (node (ref "L4") (pin "1") (pinfunction "1_1") (pintype "passive"))
      (node (ref "M1") (pin "10") (pinfunction "DCC_10") (pintype "passive"))
    )
    (net (code "79") (name "Net-(M1-DEC4)") (class "Default")
      (node (ref "C38") (pin "2") (pinfunction "2_2") (pintype "passive"))
      (node (ref "L3") (pin "2") (pinfunction "2_2") (pintype "passive"))
      (node (ref "M1") (pin "9") (pinfunction "DEC4_9") (pintype "passive"))
    )
    (net (code "80") (name "Net-(M1-P0.00{slash}XL1)") (class "Default")
      (node (ref "C53") (pin "2") (pinfunction "2_2") (pintype "passive"))
      (node (ref "M1") (pin "13") (pinfunction "P0.00/XL1_13") (pintype "passive"))
      (node (ref "X1") (pin "2") (pinfunction "2_2") (pintype "passive"))
    )
    (net (code "81") (name "Net-(M1-P0.01{slash}XL2)") (class "Default")
      (node (ref "C54") (pin "2") (pinfunction "2_2") (pintype "passive"))
      (node (ref "M1") (pin "14") (pinfunction "P0.01/XL2_14") (pintype "passive"))
      (node (ref "X1") (pin "1") (pinfunction "1_1") (pintype "passive"))
    )
    (net (code "82") (name "Net-(M1-P0.17)") (class "Default")
      (node (ref "M1") (pin "31") (pinfunction "P0.17_31") (pintype "passive"))
      (node (ref "R22") (pin "1") (pinfunction "1_1") (pintype "passive"))
    )
    (net (code "83") (name "Net-(M1-P0.18)") (class "Default")
      (node (ref "M1") (pin "32") (pinfunction "P0.18_32") (pintype "passive"))
      (node (ref "R21") (pin "1") (pinfunction "1_1") (pintype "passive"))
    )
    (net (code "84") (name "Net-(U1-PROG)") (class "Default")
      (node (ref "R9") (pin "1") (pinfunction "1_1") (pintype "passive"))
      (node (ref "U1") (pin "5") (pinfunction "PROG_5") (pintype "passive"))
    )
    (net (code "85") (name "Net-(U1-STAT)") (class "Default")
      (node (ref "R10") (pin "2") (pinfunction "2_2") (pintype "passive"))
      (node (ref "U1") (pin "1") (pinfunction "STAT_1") (pintype "open_collector"))
    )
    (net (code "86") (name "Net-(U2-BIASINV)") (class "Default")
      (node (ref "C14") (pin "1") (pinfunction "1_1") (pintype "passive"))
      (node (ref "R17") (pin "1") (pinfunction "1_1") (pintype "passive"))
      (node (ref "U2") (pin "61") (pinfunction "BIASINV_61") (pintype "bidirectional"))
    )
    (net (code "87") (name "Net-(U2-BIASREF)") (class "Default")
      (node (ref "R29") (pin "1") (pinfunction "1_1") (pintype "passive"))
      (node (ref "U2") (pin "60") (pinfunction "BIASREF_60") (pintype "input"))
    )
    (net (code "88") (name "Net-(U2-GPIO1)") (class "Default")
      (node (ref "R14") (pin "1") (pinfunction "1_1") (pintype "passive"))
      (node (ref "U2") (pin "42") (pinfunction "GPIO1_42") (pintype "bidirectional"))
    )
    (net (code "89") (name "Net-(U2-GPIO2)") (class "Default")
      (node (ref "R13") (pin "1") (pinfunction "1_1") (pintype "passive"))
      (node (ref "U2") (pin "44") (pinfunction "GPIO2_44") (pintype "bidirectional"))
    )
    (net (code "90") (name "Net-(U2-GPIO3)") (class "Default")
      (node (ref "R12") (pin "1") (pinfunction "1_1") (pintype "passive"))
      (node (ref "U2") (pin "45") (pinfunction "GPIO3_45") (pintype "bidirectional"))
    )
    (net (code "91") (name "Net-(U2-GPIO4)") (class "Default")
      (node (ref "R11") (pin "1") (pinfunction "1_1") (pintype "passive"))
      (node (ref "U2") (pin "46") (pinfunction "GPIO4_46") (pintype "bidirectional"))
    )
    (net (code "92") (name "Net-(U2-SRB1)") (class "Default")
      (node (ref "TP5") (pin "1") (pinfunction "1_1") (pintype "passive"))
      (node (ref "U2") (pin "17") (pinfunction "SRB1_17") (pintype "bidirectional"))
      (node (ref "U3") (pin "6") (pinfunction "INB-_6") (pintype "input"))
      (node (ref "U3") (pin "7") (pinfunction "OUTB_7") (pintype "output"))
    )
    (net (code "93") (name "Net-(U2-VCAP1)") (class "Default")
      (node (ref "C22") (pin "1") (pinfunction "1_1") (pintype "passive"))
      (node (ref "U2") (pin "28") (pinfunction "VCAP1_28") (pintype "passive"))
    )
    (net (code "94") (name "Net-(U2-VCAP2)") (class "Default")
      (node (ref "C21") (pin "2") (pinfunction "2_2") (pintype "passive"))
      (node (ref "U2") (pin "30") (pinfunction "VCAP2_30") (pintype "passive"))
    )
    (net (code "95") (name "Net-(U2-VCAP3)") (class "Default")
      (node (ref "C24") (pin "2") (pinfunction "2_2") (pintype "passive"))
      (node (ref "C25") (pin "2") (pinfunction "2_2") (pintype "passive"))
      (node (ref "U2") (pin "55") (pinfunction "VCAP3_55") (pintype "passive"))
    )
    (net (code "96") (name "Net-(U2-VCAP4)") (class "Default")
      (node (ref "C23") (pin "2") (pinfunction "2_2") (pintype "passive"))
      (node (ref "U2") (pin "26") (pinfunction "VCAP4_26") (pintype "output"))
    )
    (net (code "97") (name "Net-(U2-VREFP)") (class "Default")
      (node (ref "C20") (pin "1") (pinfunction "1_1") (pintype "passive"))
      (node (ref "U2") (pin "24") (pinfunction "VREFP_24") (pintype "bidirectional"))
    )
    (net (code "98") (name "Net-(U3-INA-)") (class "Default")
      (node (ref "U3") (pin "1") (pinfunction "OUTA_1") (pintype "output"))
      (node (ref "U3") (pin "2") (pinfunction "INA-_2") (pintype "input"))
    )
    (net (code "99") (name "Net-(U4-FB)") (class "Default")
      (node (ref "C19") (pin "2") (pinfunction "2_2") (pintype "passive"))
      (node (ref "R15") (pin "1") (pinfunction "1_1") (pintype "passive"))
      (node (ref "R18") (pin "2") (pinfunction "2_2") (pintype "passive"))
      (node (ref "U4") (pin "8") (pinfunction "FB_8") (pintype "input"))
    )
    (net (code "100") (name "Net-(U4-L1)") (class "Default")
      (node (ref "L1") (pin "1") (pinfunction "1_1") (pintype "passive"))
      (node (ref "U4") (pin "1") (pinfunction "L1_1") (pintype "input"))
    )
    (net (code "101") (name "Net-(U4-L2)") (class "Default")
      (node (ref "L1") (pin "2") (pinfunction "2_2") (pintype "passive"))
      (node (ref "U4") (pin "10") (pinfunction "L2_10") (pintype "input"))
    )
    (net (code "102") (name "Net-(U4-PG)") (class "Default")
      (node (ref "R16") (pin "1") (pinfunction "1_1") (pintype "passive"))
      (node (ref "U4") (pin "5") (pinfunction "PG_5") (pintype "output"))
    )
    (net (code "103") (name "Net-(U4-VAUX)") (class "Default")
      (node (ref "C18") (pin "2") (pinfunction "2_2") (pintype "passive"))
      (node (ref "U4") (pin "6") (pinfunction "VAUX_6") (pintype "passive"))
    )
    (net (code "104") (name "unconnected-(C_test3-Pad2)") (class "Default")
      (node (ref "C_test3") (pin "2") (pinfunction "2_2") (pintype "passive"))
    )
    (net (code "105") (name "unconnected-(C_test4-Pad2)") (class "Default")
      (node (ref "C_test4") (pin "2") (pinfunction "2_2") (pintype "passive"))
    )
    (net (code "106") (name "unconnected-(C_test5-Pad1)") (class "Default")
      (node (ref "C_test5") (pin "1") (pinfunction "1_1") (pintype "passive"))
    )
    (net (code "107") (name "unconnected-(C_test6-Pad1)") (class "Default")
      (node (ref "C_test6") (pin "1") (pinfunction "1_1") (pintype "passive"))
    )
    (net (code "108") (name "unconnected-(D1_3-NC-Pad2)") (class "Default")
      (node (ref "D1_3") (pin "2") (pinfunction "NC_2") (pintype "passive"))
    )
    (net (code "109") (name "unconnected-(D1_4-NC-Pad2)") (class "Default")
      (node (ref "D1_4") (pin "2") (pinfunction "NC_2") (pintype "passive"))
    )
    (net (code "110") (name "unconnected-(D1_5-NC-Pad2)") (class "Default")
      (node (ref "D1_5") (pin "2") (pinfunction "NC_2") (pintype "passive"))
    )
    (net (code "111") (name "unconnected-(D1_6-NC-Pad2)") (class "Default")
      (node (ref "D1_6") (pin "2") (pinfunction "NC_2") (pintype "passive"))
    )
    (net (code "112") (name "unconnected-(D2_3-NC-Pad2)") (class "Default")
      (node (ref "D2_3") (pin "2") (pinfunction "NC_2") (pintype "passive"))
    )
    (net (code "113") (name "unconnected-(D2_4-NC-Pad2)") (class "Default")
      (node (ref "D2_4") (pin "2") (pinfunction "NC_2") (pintype "passive"))
    )
    (net (code "114") (name "unconnected-(D2_5-NC-Pad2)") (class "Default")
      (node (ref "D2_5") (pin "2") (pinfunction "NC_2") (pintype "passive"))
    )
    (net (code "115") (name "unconnected-(D2_6-NC-Pad2)") (class "Default")
      (node (ref "D2_6") (pin "2") (pinfunction "NC_2") (pintype "passive"))
    )
    (net (code "116") (name "unconnected-(H1-D+-Pad3)") (class "Default")
      (node (ref "H1") (pin "3") (pinfunction "D+_3") (pintype "passive"))
    )
    (net (code "117") (name "unconnected-(H1-D--Pad2)") (class "Default")
      (node (ref "H1") (pin "2") (pinfunction "D-_2") (pintype "passive"))
    )
    (net (code "118") (name "unconnected-(IC2-FC-Pad1)") (class "Default")
      (node (ref "IC2") (pin "1") (pinfunction "FC_1") (pintype "passive"))
    )
    (net (code "119") (name "unconnected-(IC2-LV-Pad6)") (class "Default")
      (node (ref "IC2") (pin "6") (pinfunction "LV_6") (pintype "passive"))
    )
    (net (code "120") (name "unconnected-(IC2-OSC-Pad7)") (class "Default")
      (node (ref "IC2") (pin "7") (pinfunction "OSC_7") (pintype "passive"))
    )
    (net (code "121") (name "unconnected-(J7-DAT1-Pad8)") (class "Default")
      (node (ref "J7") (pin "8") (pinfunction "DAT1_8") (pintype "bidirectional"))
    )
    (net (code "122") (name "unconnected-(J7-DAT2-Pad1)") (class "Default")
      (node (ref "J7") (pin "1") (pinfunction "DAT2_1") (pintype "bidirectional"))
    )
    (net (code "123") (name "unconnected-(M1-P0.02-Pad15)") (class "Default")
      (node (ref "M1") (pin "15") (pinfunction "P0.02_15") (pintype "passive"))
    )
    (net (code "124") (name "unconnected-(M1-P0.03-Pad16)") (class "Default")
      (node (ref "M1") (pin "16") (pinfunction "P0.03_16") (pintype "passive"))
    )
    (net (code "125") (name "unconnected-(M1-P0.05-Pad18)") (class "Default")
      (node (ref "M1") (pin "18") (pinfunction "P0.05_18") (pintype "passive"))
    )
    (net (code "126") (name "unconnected-(M1-P0.06-Pad19)") (class "Default")
      (node (ref "M1") (pin "19") (pinfunction "P0.06_19") (pintype "passive"))
    )
    (net (code "127") (name "unconnected-(M1-P0.07-Pad20)") (class "Default")
      (node (ref "M1") (pin "20") (pinfunction "P0.07_20") (pintype "passive"))
    )
    (net (code "128") (name "unconnected-(M1-P0.08-Pad21)") (class "Default")
      (node (ref "M1") (pin "21") (pinfunction "P0.08_21") (pintype "passive"))
    )
    (net (code "129") (name "unconnected-(M1-P0.09-Pad22)") (class "Default")
      (node (ref "M1") (pin "22") (pinfunction "P0.09_22") (pintype "passive"))
    )
    (net (code "130") (name "unconnected-(M1-P0.10-Pad23)") (class "Default")
      (node (ref "M1") (pin "23") (pinfunction "P0.10_23") (pintype "passive"))
    )
    (net (code "131") (name "unconnected-(M1-P0.19-Pad33)") (class "Default")
      (node (ref "M1") (pin "33") (pinfunction "P0.19_33") (pintype "passive"))
    )
    (net (code "132") (name "unconnected-(M1-P0.21{slash}RESET-Pad35)") (class "Default")
      (node (ref "M1") (pin "35") (pinfunction "P0.21/RESET_35") (pintype "passive"))
    )
    (net (code "133") (name "unconnected-(M1-P0.23-Pad41)") (class "Default")
      (node (ref "M1") (pin "41") (pinfunction "P0.23_41") (pintype "passive"))
    )
    (net (code "134") (name "unconnected-(M1-P0.24-Pad40)") (class "Default")
      (node (ref "M1") (pin "40") (pinfunction "P0.24_40") (pintype "passive"))
    )
    (net (code "135") (name "unconnected-(M1-P0.25-Pad2)") (class "Default")
      (node (ref "M1") (pin "2") (pinfunction "P0.25_2") (pintype "passive"))
    )
    (net (code "136") (name "unconnected-(M1-P0.26-Pad3)") (class "Default")
      (node (ref "M1") (pin "3") (pinfunction "P0.26_3") (pintype "passive"))
    )
    (net (code "137") (name "unconnected-(M1-P0.27-Pad4)") (class "Default")
      (node (ref "M1") (pin "4") (pinfunction "P0.27_4") (pintype "passive"))
    )
    (net (code "138") (name "unconnected-(M1-P0.28-Pad5)") (class "Default")
      (node (ref "M1") (pin "5") (pinfunction "P0.28_5") (pintype "passive"))
    )
    (net (code "139") (name "unconnected-(M1-P0.29-Pad6)") (class "Default")
      (node (ref "M1") (pin "6") (pinfunction "P0.29_6") (pintype "passive"))
    )
    (net (code "140") (name "unconnected-(M1-P0.30-Pad7)") (class "Default")
      (node (ref "M1") (pin "7") (pinfunction "P0.30_7") (pintype "passive"))
    )
    (net (code "141") (name "unconnected-(M1-P0.31-Pad8)") (class "Default")
      (node (ref "M1") (pin "8") (pinfunction "P0.31_8") (pintype "passive"))
    )
    (net (code "142") (name "unconnected-(S1-ON_1-Pad1)") (class "Default")
      (node (ref "S1") (pin "1") (pinfunction "ON_1_1") (pintype "passive"))
    )
    (net (code "143") (name "unconnected-(U2-CLK-Pad37)") (class "Default")
      (node (ref "U2") (pin "37") (pinfunction "CLK_37") (pintype "input+no_connect"))
    )
    (net (code "144") (name "unconnected-(U2-IN4N-Pad9)") (class "Default")
      (node (ref "U2") (pin "9") (pinfunction "IN4N_9") (pintype "input+no_connect"))
    )
    (net (code "145") (name "unconnected-(U2-IN4P-Pad10)") (class "Default")
      (node (ref "U2") (pin "10") (pinfunction "IN4P_10") (pintype "input+no_connect"))
    )
    (net (code "146") (name "unconnected-(U2-IN5N-Pad7)") (class "Default")
      (node (ref "U2") (pin "7") (pinfunction "IN5N_7") (pintype "input+no_connect"))
    )
    (net (code "147") (name "unconnected-(U2-IN5P-Pad8)") (class "Default")
      (node (ref "U2") (pin "8") (pinfunction "IN5P_8") (pintype "input+no_connect"))
    )
    (net (code "148") (name "unconnected-(U2-IN6N-Pad5)") (class "Default")
      (node (ref "U2") (pin "5") (pinfunction "IN6N_5") (pintype "input+no_connect"))
    )
    (net (code "149") (name "unconnected-(U2-IN6P-Pad6)") (class "Default")
      (node (ref "U2") (pin "6") (pinfunction "IN6P_6") (pintype "input+no_connect"))
    )
    (net (code "150") (name "unconnected-(U2-IN7N-Pad3)") (class "Default")
      (node (ref "U2") (pin "3") (pinfunction "IN7N_3") (pintype "input+no_connect"))
    )
    (net (code "151") (name "unconnected-(U2-IN7P-Pad4)") (class "Default")
      (node (ref "U2") (pin "4") (pinfunction "IN7P_4") (pintype "input+no_connect"))
    )
    (net (code "152") (name "unconnected-(U2-IN8N-Pad1)") (class "Default")
      (node (ref "U2") (pin "1") (pinfunction "IN8N_1") (pintype "input+no_connect"))
    )
    (net (code "153") (name "unconnected-(U2-IN8P-Pad2)") (class "Default")
      (node (ref "U2") (pin "2") (pinfunction "IN8P_2") (pintype "input+no_connect"))
    )
    (net (code "154") (name "unconnected-(U2-NC-Pad27)") (class "Default")
      (node (ref "U2") (pin "27") (pinfunction "NC_27") (pintype "passive"))
    )
    (net (code "155") (name "unconnected-(U2-NC-Pad29)") (class "Default")
      (node (ref "U2") (pin "29") (pinfunction "NC_29") (pintype "passive"))
    )
    (net (code "156") (name "unconnected-(U2-RESERVED-Pad64)") (class "Default")
      (node (ref "U2") (pin "64") (pinfunction "RESERVED_64") (pintype "output"))
    )
    (net (code "157") (name "unconnected-(U2-SRB2-Pad18)") (class "Default")
      (node (ref "U2") (pin "18") (pinfunction "SRB2_18") (pintype "bidirectional+no_connect"))
    )
  )
)
